# pc_healthypi_5_3.net
KiCad netlist of a schematic drawn in EAGLE
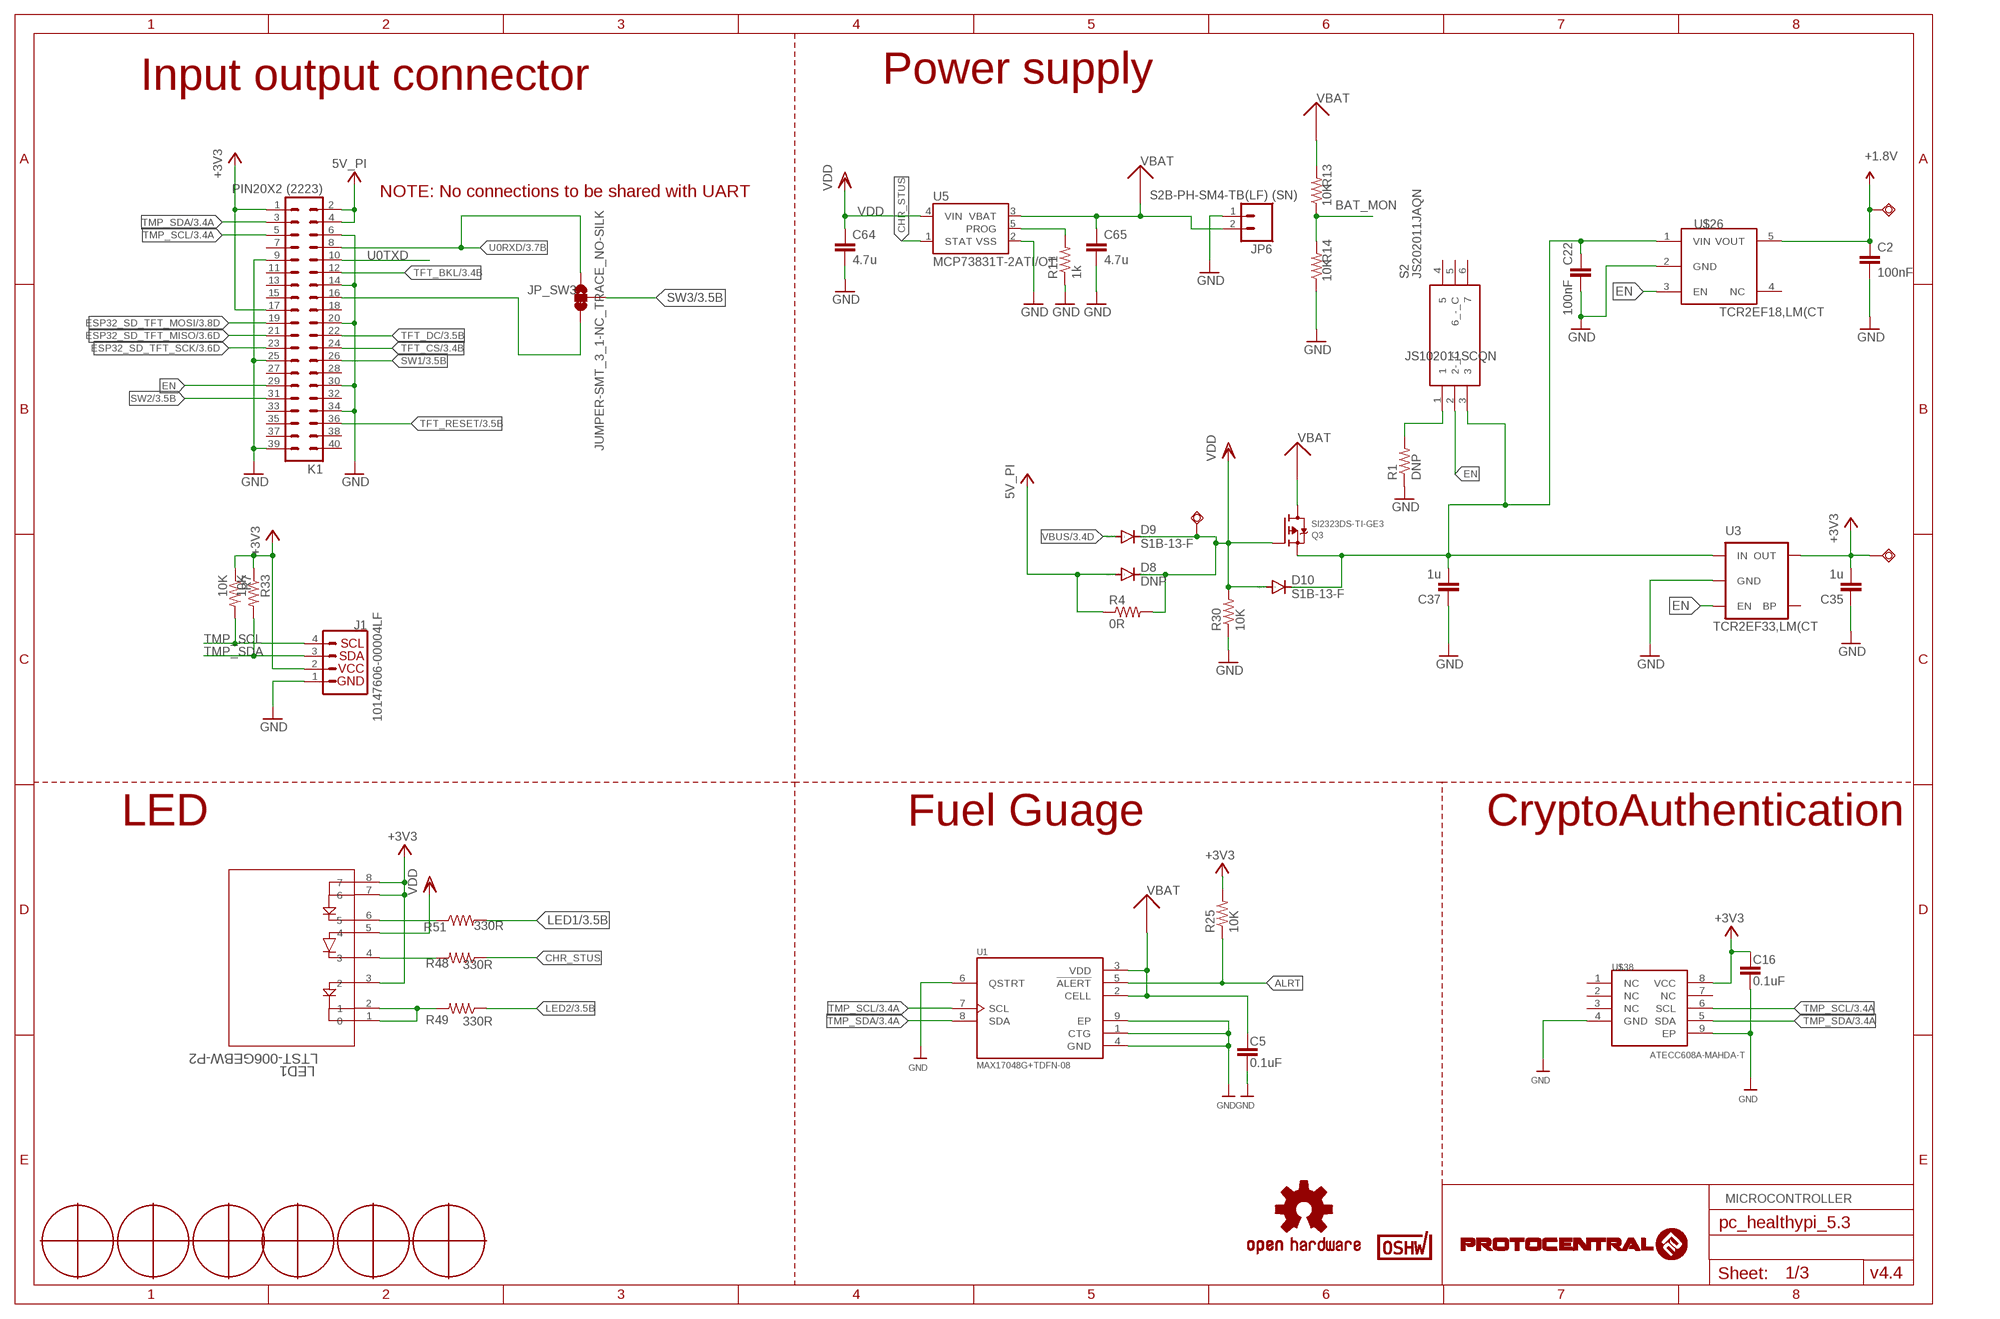
[diagram p0: schematic, sheet 1]
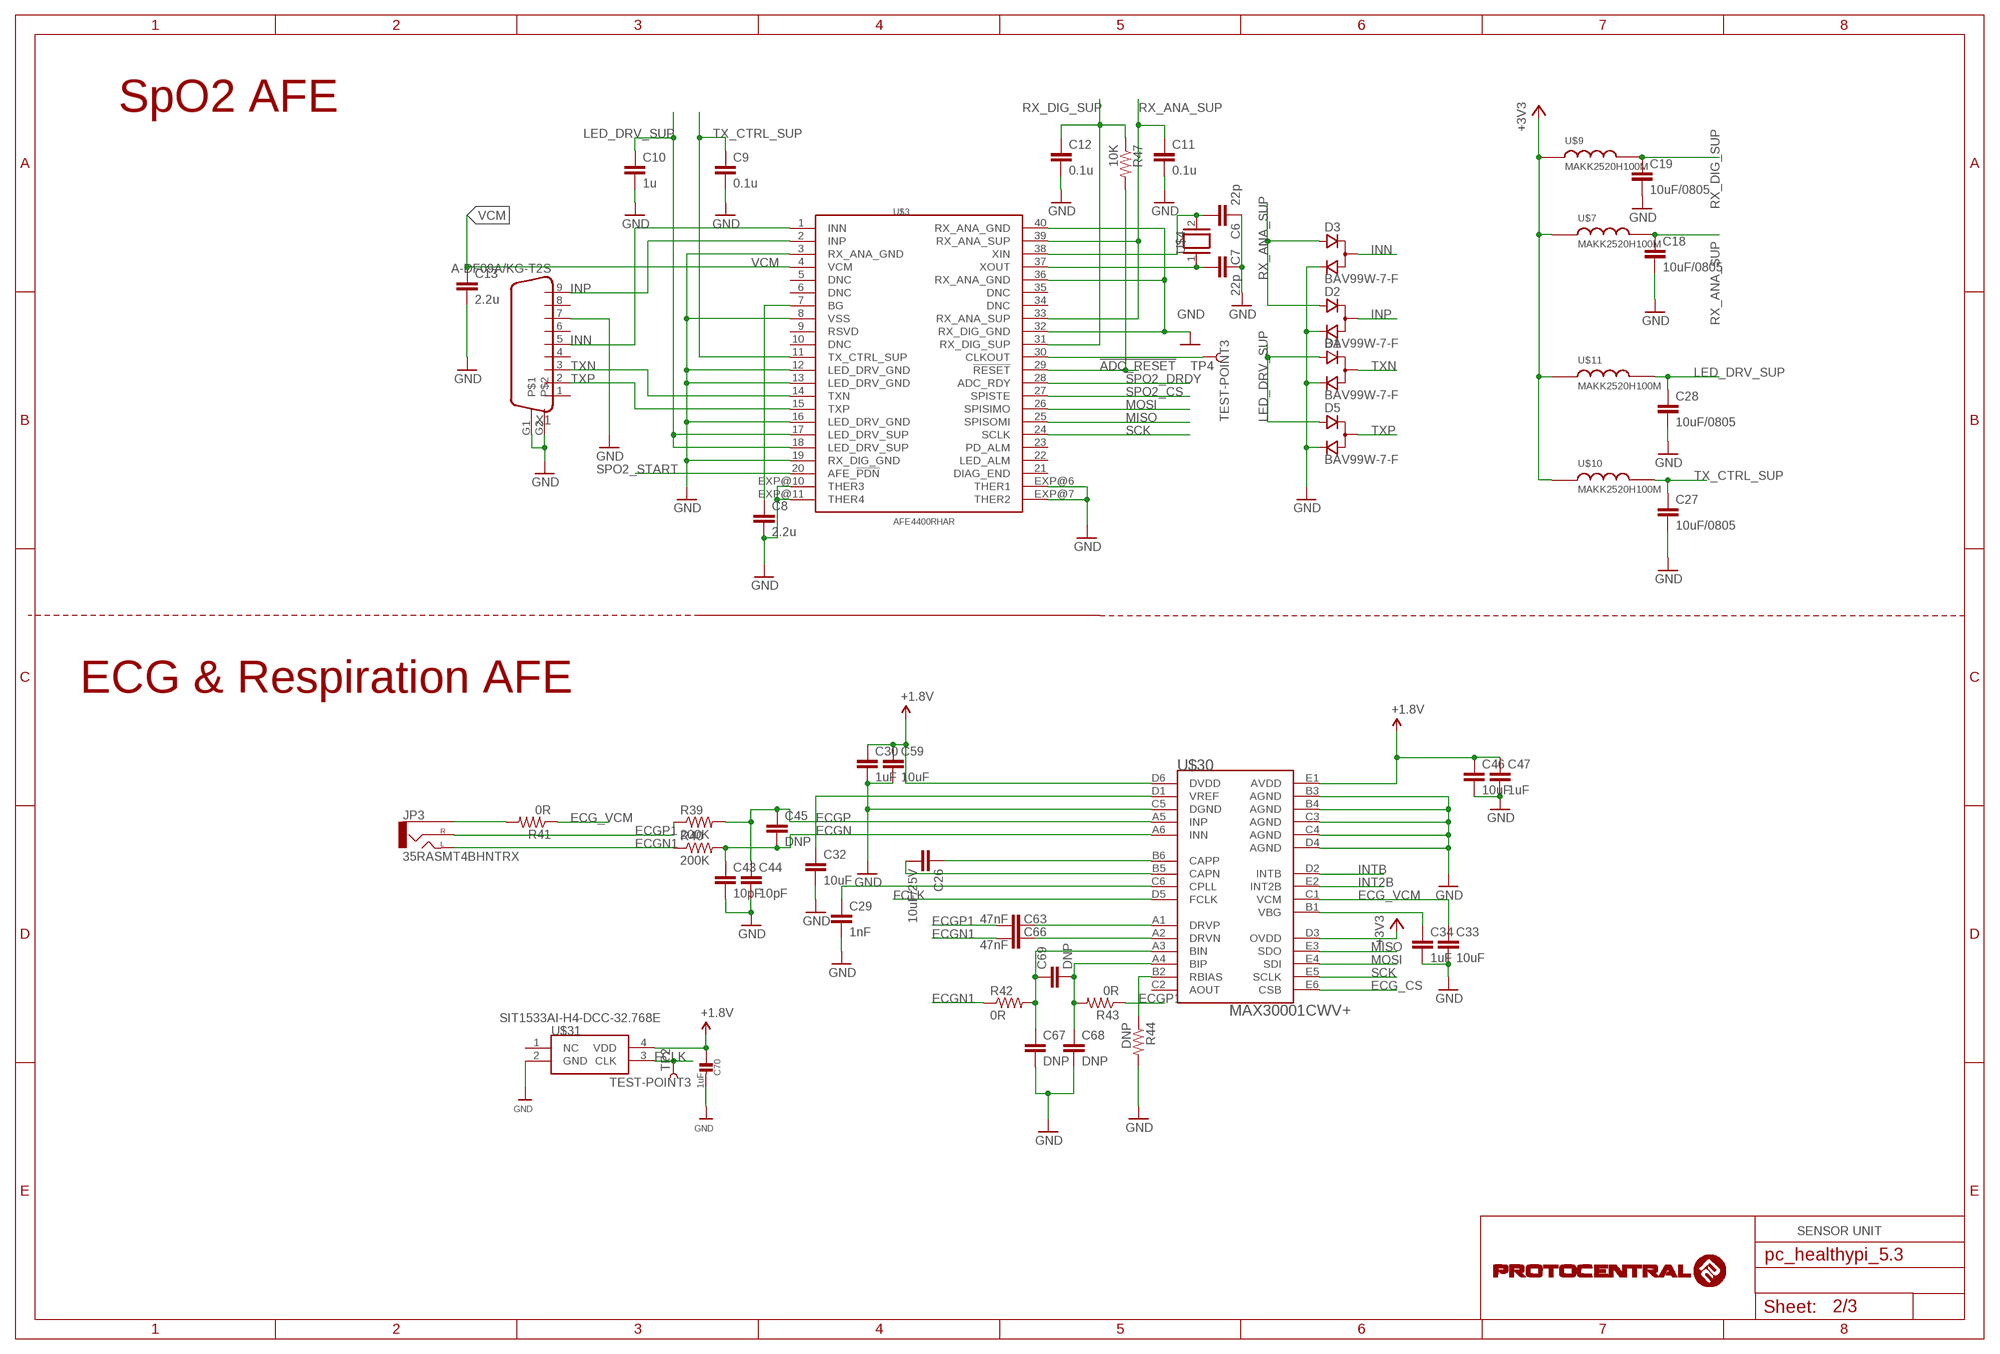
[diagram p1: schematic, sheet 2]
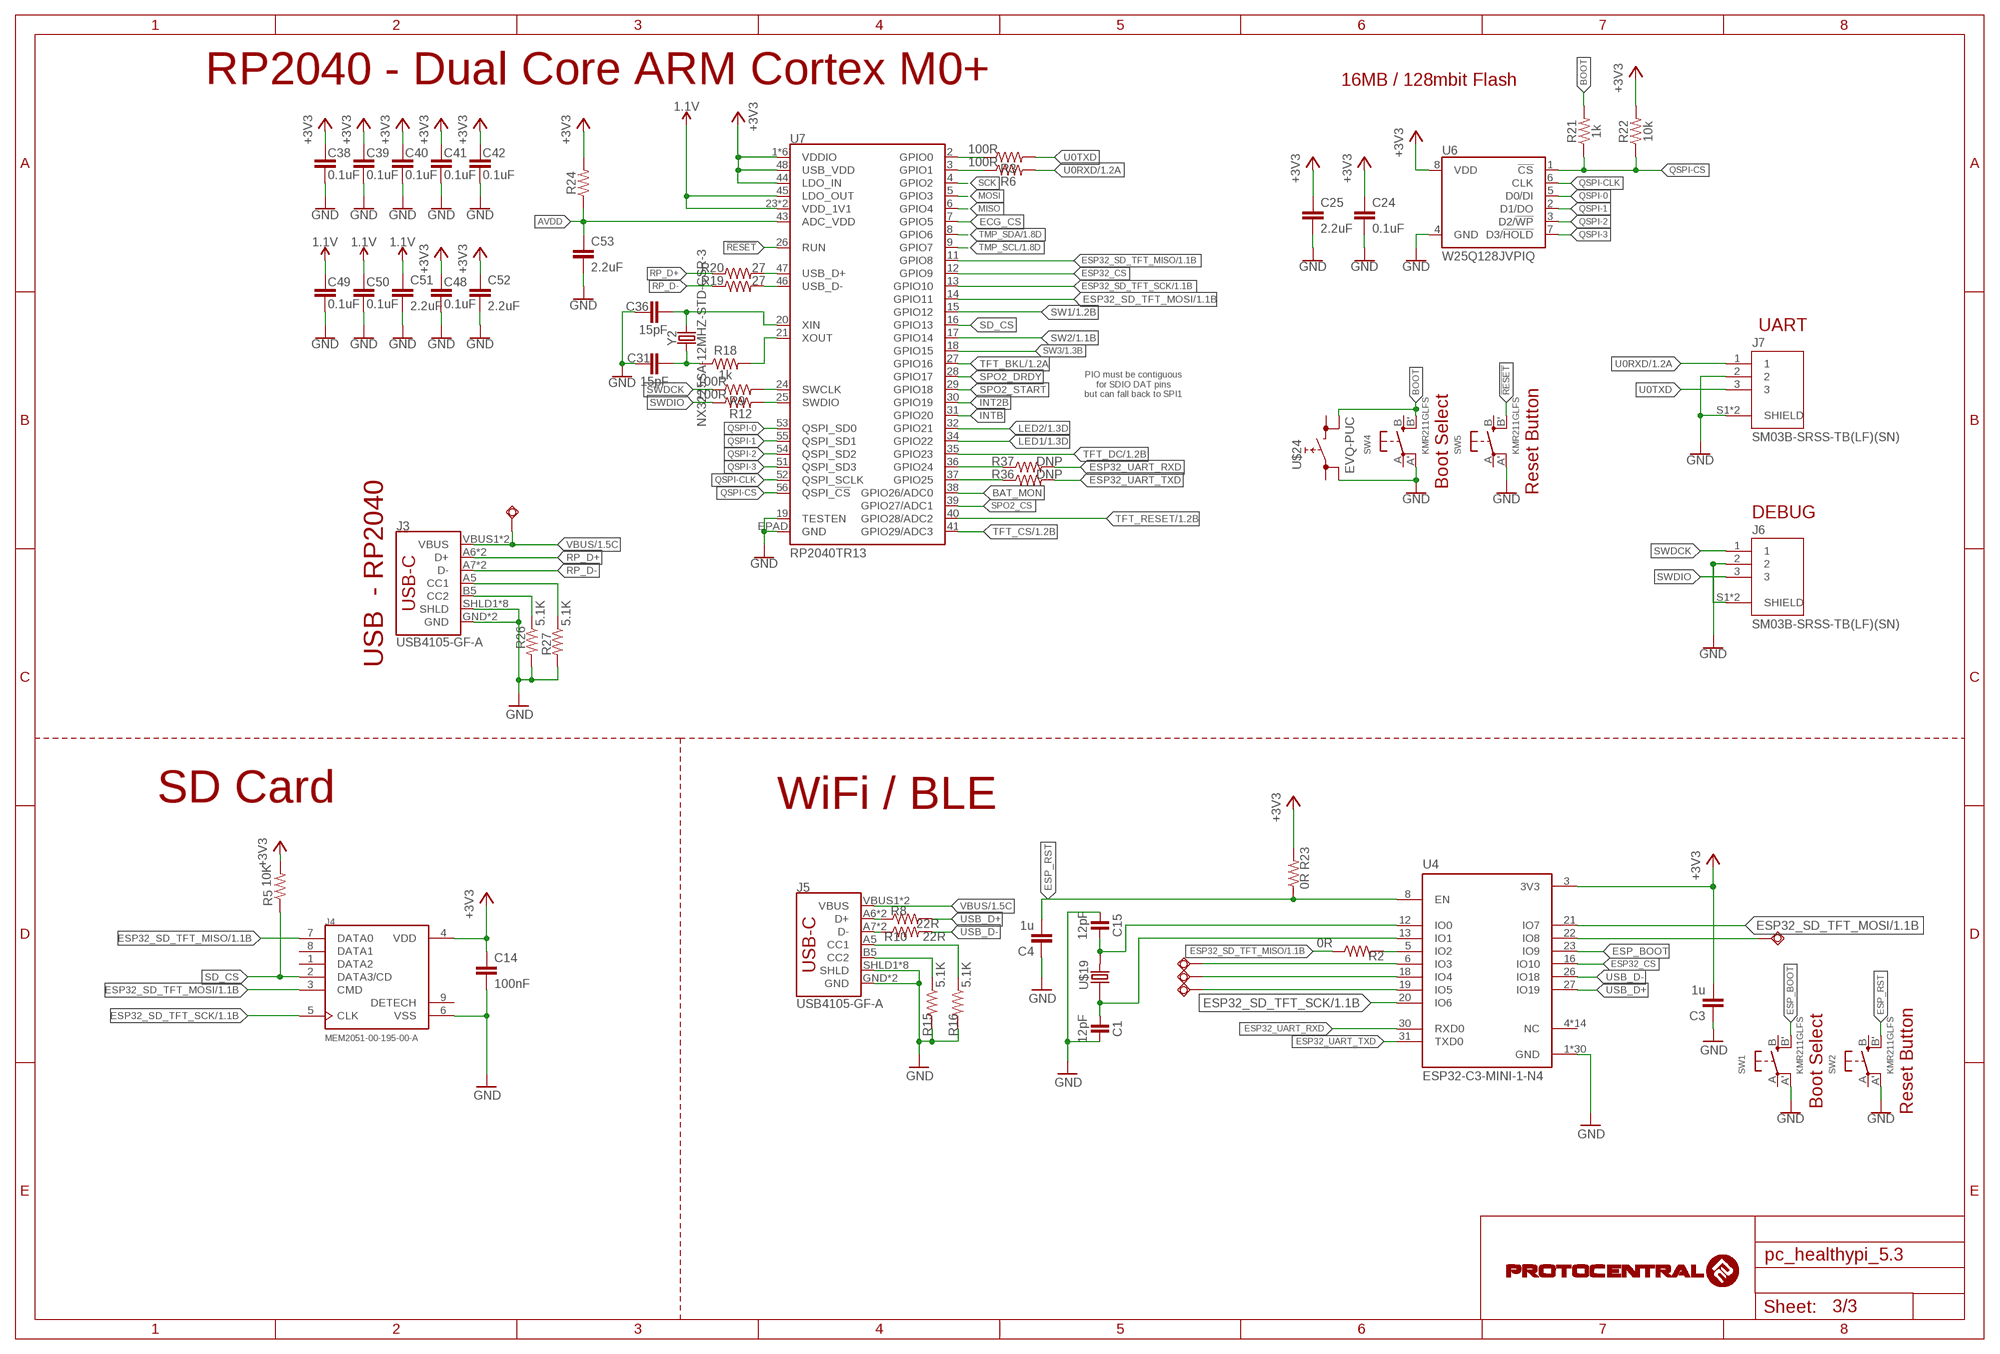
[diagram p2: schematic, sheet 3]

(export (version "E")
  (design (tool "Eeschema 10.0.6"))
  (components
    (comp (ref "C2")
      (value "100nF")
      (footprint "eagle-import:C0402")
      (libsource (lib "eagle-import") (part "rcl_334_C-EUC0402"))
    )
    (comp (ref "C5")
      (value "0.1uF")
      (footprint "eagle-import:0402-TIGHT")
      (libsource (lib "eagle-import") (part "0.1UF-0402T-6.3V-10%-X7R"))
    )
    (comp (ref "C16")
      (value "0.1uF")
      (footprint "eagle-import:0402-TIGHT")
      (libsource (lib "eagle-import") (part "0.1UF-0402T-6.3V-10%-X7R"))
    )
    (comp (ref "C22")
      (value "100nF")
      (footprint "eagle-import:C0402")
      (libsource (lib "eagle-import") (part "rcl_334_C-EUC0402"))
    )
    (comp (ref "C35")
      (value "1u")
      (footprint "eagle-import:C0402")
      (libsource (lib "eagle-import") (part "rcl_334_C-EUC0402"))
    )
    (comp (ref "C37")
      (value "1u")
      (footprint "eagle-import:C0402")
      (libsource (lib "eagle-import") (part "rcl_334_C-EUC0402"))
    )
    (comp (ref "C64")
      (value "4.7u")
      (footprint "eagle-import:C0805")
      (libsource (lib "eagle-import") (part "rcl_334_C-EUC0805"))
    )
    (comp (ref "C65")
      (value "4.7u")
      (footprint "eagle-import:C0805")
      (libsource (lib "eagle-import") (part "rcl_334_C-EUC0805"))
    )
    (comp (ref "D8")
      (value "DNP")
      (footprint "eagle-import:SOD-123_MINI-SMA")
      (libsource (lib "eagle-import") (part "CGRM400-G1"))
    )
    (comp (ref "D9")
      (value "S1B-13-F")
      (footprint "eagle-import:SOD-123_MINI-SMA")
      (libsource (lib "eagle-import") (part "CGRM400-G1"))
    )
    (comp (ref "D10")
      (value "S1B-13-F")
      (footprint "eagle-import:SOD-123_MINI-SMA")
      (libsource (lib "eagle-import") (part "CGRM400-G1"))
    )
    (comp (ref "J1")
      (value "10147606-00004LF")
      (footprint "eagle-import:JST04_1MM_RA")
      (libsource (lib "eagle-import") (part "QWIIC_CONNECTORJS-1MM"))
    )
    (comp (ref "JP6")
      (value "S2B-PH-SM4-TB(LF) (SN)")
      (footprint "eagle-import:JST-2-SMD")
      (libsource (lib "eagle-import") (part "M02-JST-2MM-SMT"))
    )
    (comp (ref "JP_SW3")
      (value "JUMPER-SMT_3_1-NC_TRACE_NO-SILK")
      (footprint "eagle-import:SMT-JUMPER_3_1-NC_TRACE_NO-SILK")
      (libsource (lib "eagle-import") (part "JUMPER-SMT_3_1-NC_TRACE_NO-SILK"))
    )
    (comp (ref "K1")
      (value "PIN20X2 (2223)")
      (footprint "eagle-import:PIN_20X2")
      (libsource (lib "eagle-import") (part "PIN20X2"))
    )
    (comp (ref "LED1")
      (value "LTST-006GEBW-P2")
      (footprint "eagle-import:LTST-008BGEW_LTO")
      (fields (field (name "COPYRIGHT") "Copyright (C) 2023 Ultra Librarian. All rights reserved."))
      (libsource (lib "eagle-import") (part "LTST-006GEBW-P2"))
    )
    (comp (ref "Q3")
      (value "SI2323DS-TI-GE3")
      (footprint "eagle-import:SOT23-R")
      (libsource (lib "eagle-import") (part "MOSFET-P"))
    )
    (comp (ref "R1")
      (value "DNP")
      (footprint "eagle-import:R0402")
      (libsource (lib "eagle-import") (part "rcl_334_R-US_R0402"))
    )
    (comp (ref "R4")
      (value "0R")
      (footprint "eagle-import:0805")
      (libsource (lib "eagle-import") (part "RESISTOR0805-RES"))
    )
    (comp (ref "R7")
      (value "10K")
      (footprint "eagle-import:R0402")
      (libsource (lib "eagle-import") (part "rcl_334_R-US_R0402"))
    )
    (comp (ref "R11")
      (value "1k")
      (footprint "eagle-import:R0402")
      (libsource (lib "eagle-import") (part "rcl_334_R-US_R0402"))
    )
    (comp (ref "R13")
      (value "10K")
      (footprint "eagle-import:R0402")
      (libsource (lib "eagle-import") (part "rcl_334_R-US_R0402"))
    )
    (comp (ref "R14")
      (value "10K")
      (footprint "eagle-import:R0402")
      (libsource (lib "eagle-import") (part "rcl_334_R-US_R0402"))
    )
    (comp (ref "R25")
      (value "10K")
      (footprint "eagle-import:0402-RES")
      (libsource (lib "eagle-import") (part "RESISTOR0402-RES"))
    )
    (comp (ref "R30")
      (value "10K")
      (footprint "eagle-import:R0402")
      (libsource (lib "eagle-import") (part "rcl_334_R-US_R0402"))
    )
    (comp (ref "R33")
      (value "10K")
      (footprint "eagle-import:R0402")
      (libsource (lib "eagle-import") (part "rcl_334_R-US_R0402"))
    )
    (comp (ref "R48")
      (value "330R")
      (footprint "eagle-import:0402-RES")
      (libsource (lib "eagle-import") (part "RESISTOR0402-RES"))
    )
    (comp (ref "R49")
      (value "330R")
      (footprint "eagle-import:0402-RES")
      (libsource (lib "eagle-import") (part "RESISTOR0402-RES"))
    )
    (comp (ref "R51")
      (value "330R")
      (footprint "eagle-import:0402-RES")
      (libsource (lib "eagle-import") (part "RESISTOR0402-RES"))
    )
    (comp (ref "S2")
      (value "JS202011JAQN")
      (footprint "eagle-import:JS202011JAQN")
      (fields (field (name "MF") "C&K"))
      (libsource (lib "eagle-import") (part "JS202011JAQN"))
    )
    (comp (ref "SWIO1")
      (value "TPSQTP11R")
      (footprint "eagle-import:TP11R")
      (libsource (lib "eagle-import") (part "TPSQTP11R"))
    )
    (comp (ref "SWIO5")
      (value "TPSQTP11R")
      (footprint "eagle-import:TP11R")
      (libsource (lib "eagle-import") (part "TPSQTP11R"))
    )
    (comp (ref "SWIO7")
      (value "TPSQTP11R")
      (footprint "eagle-import:TP11R")
      (libsource (lib "eagle-import") (part "TPSQTP11R"))
    )
    (comp (ref "U$1")
      (value "FUDCIALPOINTS")
      (footprint "eagle-import:FIDUCIALPOINTS")
      (libsource (lib "eagle-import") (part "circuitects_38825256_FUDCIALPOINTS"))
    )
    (comp (ref "U$5")
      (value "OSHW-LOGOM")
      (footprint "eagle-import:OSHW-LOGO-M")
      (libsource (lib "eagle-import") (part "OSHW-LOGOM"))
    )
    (comp (ref "U$13")
      (value "CERT-SMALL")
      (footprint "eagle-import:CERT-SMALL-SILK")
      (libsource (lib "eagle-import") (part "CERT-SMALL"))
    )
    (comp (ref "U$21")
      (value "FUDCIALPOINTS")
      (footprint "eagle-import:FIDUCIALPOINTS")
      (libsource (lib "eagle-import") (part "FUDCIALPOINTS"))
    )
    (comp (ref "U$23")
      (value "FUDCIALPOINTS")
      (footprint "eagle-import:FIDUCIALPOINTS")
      (libsource (lib "eagle-import") (part "circuitects_38825256_FUDCIALPOINTS"))
    )
    (comp (ref "U$25")
      (value "FUDCIALPOINTS")
      (footprint "eagle-import:FIDUCIALPOINTS")
      (libsource (lib "eagle-import") (part "circuitects_38825256_FUDCIALPOINTS"))
    )
    (comp (ref "U$26")
      (value "TCR2EF18,LM(CT")
      (footprint "eagle-import:SOT95P285X140-5N")
      (libsource (lib "eagle-import") (part "AP7354D-18W5-7"))
    )
    (comp (ref "U$28")
      (value "FUDCIALPOINTS")
      (footprint "eagle-import:FIDUCIALPOINTS")
      (libsource (lib "eagle-import") (part "FUDCIALPOINTS"))
    )
    (comp (ref "U$29")
      (value "FUDCIALPOINTS")
      (footprint "eagle-import:FIDUCIALPOINTS")
      (libsource (lib "eagle-import") (part "FUDCIALPOINTS"))
    )
    (comp (ref "U$38")
      (value "ATECC608A-MAHDA-T")
      (footprint "eagle-import:PSON50P200X300X60-9N")
      (libsource (lib "eagle-import") (part "ATECC608B-TFLXTLS"))
    )
    (comp (ref "U1")
      (value "MAX17048G+TDFN-08")
      (footprint "eagle-import:SON50P200X200X80-9N")
      (fields (field (name "MF") "Analog Devices") (field (name "MP") "MAX17048G+"))
      (libsource (lib "eagle-import") (part "MAX17048G+TDFN-08"))
    )
    (comp (ref "U3")
      (value "TCR2EF33,LM(CT")
      (footprint "eagle-import:SOT23-5")
      (libsource (lib "eagle-import") (part "V_REG_LDOSMD"))
    )
    (comp (ref "U5")
      (value "MCP73831T-2ATI/OT")
      (footprint "eagle-import:SOT23-5")
      (libsource (lib "eagle-import") (part "MCP73831"))
    )
    (comp (ref "C6")
      (value "22p")
      (footprint "eagle-import:C0402")
      (libsource (lib "eagle-import") (part "rcl_334_C-EUC0402"))
    )
    (comp (ref "C7")
      (value "22p")
      (footprint "eagle-import:C0402")
      (libsource (lib "eagle-import") (part "rcl_334_C-EUC0402"))
    )
    (comp (ref "C8")
      (value "2.2u")
      (footprint "eagle-import:C0402")
      (libsource (lib "eagle-import") (part "rcl_334_C-EUC0402"))
    )
    (comp (ref "C9")
      (value "0.1u")
      (footprint "eagle-import:C0402")
      (libsource (lib "eagle-import") (part "rcl_334_C-EUC0402"))
    )
    (comp (ref "C10")
      (value "1u")
      (footprint "eagle-import:C0805")
      (libsource (lib "eagle-import") (part "rcl_334_C-EUC0805"))
    )
    (comp (ref "C11")
      (value "0.1u")
      (footprint "eagle-import:C0402")
      (libsource (lib "eagle-import") (part "rcl_334_C-EUC0402"))
    )
    (comp (ref "C12")
      (value "0.1u")
      (footprint "eagle-import:C0402")
      (libsource (lib "eagle-import") (part "rcl_334_C-EUC0402"))
    )
    (comp (ref "C13")
      (value "2.2u")
      (footprint "eagle-import:C0402")
      (libsource (lib "eagle-import") (part "rcl_334_C-EUC0402"))
    )
    (comp (ref "C18")
      (value "10uF/0805")
      (footprint "eagle-import:C0805")
      (libsource (lib "eagle-import") (part "rcl_334_C-EUC0805"))
    )
    (comp (ref "C19")
      (value "10uF/0805")
      (footprint "eagle-import:C0805")
      (libsource (lib "eagle-import") (part "rcl_334_C-EUC0805"))
    )
    (comp (ref "C26")
      (value "10uF/25V")
      (footprint "eagle-import:C0805")
      (libsource (lib "eagle-import") (part "rcl_334_C-EUC0805"))
    )
    (comp (ref "C27")
      (value "10uF/0805")
      (footprint "eagle-import:C0805")
      (libsource (lib "eagle-import") (part "rcl_334_C-EUC0805"))
    )
    (comp (ref "C28")
      (value "10uF/0805")
      (footprint "eagle-import:C0805")
      (libsource (lib "eagle-import") (part "rcl_334_C-EUC0805"))
    )
    (comp (ref "C29")
      (value "1nF")
      (footprint "eagle-import:C0402")
      (libsource (lib "eagle-import") (part "rcl_334_C-EUC0402"))
    )
    (comp (ref "C30")
      (value "1uF")
      (footprint "eagle-import:C0402")
      (libsource (lib "eagle-import") (part "rcl_334_C-EUC0402"))
    )
    (comp (ref "C32")
      (value "10uF")
      (footprint "eagle-import:C0805")
      (libsource (lib "eagle-import") (part "rcl_334_C-EUC0805"))
    )
    (comp (ref "C33")
      (value "10uF")
      (footprint "eagle-import:C0805")
      (libsource (lib "eagle-import") (part "rcl_334_C-EUC0805"))
    )
    (comp (ref "C34")
      (value "1uF")
      (footprint "eagle-import:C0402")
      (libsource (lib "eagle-import") (part "rcl_334_C-EUC0402"))
    )
    (comp (ref "C43")
      (value "10pF")
      (footprint "eagle-import:C0402")
      (libsource (lib "eagle-import") (part "rcl_334_C-EUC0402"))
    )
    (comp (ref "C44")
      (value "10pF")
      (footprint "eagle-import:C0402")
      (libsource (lib "eagle-import") (part "rcl_334_C-EUC0402"))
    )
    (comp (ref "C45")
      (value "DNP")
      (footprint "eagle-import:C0402")
      (libsource (lib "eagle-import") (part "rcl_334_C-EUC0402"))
    )
    (comp (ref "C46")
      (value "10uF")
      (footprint "eagle-import:C0805")
      (libsource (lib "eagle-import") (part "rcl_334_C-EUC0805"))
    )
    (comp (ref "C47")
      (value "1uF")
      (footprint "eagle-import:C0402")
      (libsource (lib "eagle-import") (part "rcl_334_C-EUC0402"))
    )
    (comp (ref "C59")
      (value "10uF")
      (footprint "eagle-import:C0805")
      (libsource (lib "eagle-import") (part "rcl_334_C-EUC0805"))
    )
    (comp (ref "C63")
      (value "47nF")
      (footprint "eagle-import:C0402")
      (libsource (lib "eagle-import") (part "rcl_334_C-EUC0402"))
    )
    (comp (ref "C66")
      (value "47nF")
      (footprint "eagle-import:C0402")
      (libsource (lib "eagle-import") (part "rcl_334_C-EUC0402"))
    )
    (comp (ref "C67")
      (value "DNP")
      (footprint "eagle-import:C0402")
      (libsource (lib "eagle-import") (part "rcl_334_C-EUC0402"))
    )
    (comp (ref "C68")
      (value "DNP")
      (footprint "eagle-import:C0402")
      (libsource (lib "eagle-import") (part "rcl_334_C-EUC0402"))
    )
    (comp (ref "C69")
      (value "DNP")
      (footprint "eagle-import:C0402")
      (libsource (lib "eagle-import") (part "rcl_334_C-EUC0402"))
    )
    (comp (ref "C70")
      (value "1uF")
      (footprint "eagle-import:0402")
      (libsource (lib "eagle-import") (part "CAP_CERAMIC0402"))
    )
    (comp (ref "D1")
      (value "BAV99W-7-F")
      (footprint "eagle-import:SOT323")
      (libsource (lib "eagle-import") (part "D_ACACSOT323"))
    )
    (comp (ref "D2")
      (value "BAV99W-7-F")
      (footprint "eagle-import:SOT323")
      (libsource (lib "eagle-import") (part "D_ACACSOT323"))
    )
    (comp (ref "D3")
      (value "BAV99W-7-F")
      (footprint "eagle-import:SOT323")
      (libsource (lib "eagle-import") (part "D_ACACSOT323"))
    )
    (comp (ref "D5")
      (value "BAV99W-7-F")
      (footprint "eagle-import:SOT323")
      (libsource (lib "eagle-import") (part "D_ACACSOT323"))
    )
    (comp (ref "JP3")
      (value "35RASMT4BHNTRX")
      (footprint "eagle-import:AUDIO-JACK-3.5MM-SMD")
      (libsource (lib "eagle-import") (part "AUDIO-JACKSMD2"))
    )
    (comp (ref "R39")
      (value "200K")
      (footprint "eagle-import:0805")
      (libsource (lib "eagle-import") (part "RESISTOR0805-RES"))
    )
    (comp (ref "R40")
      (value "200K")
      (footprint "eagle-import:0805")
      (libsource (lib "eagle-import") (part "RESISTOR0805-RES"))
    )
    (comp (ref "R41")
      (value "0R")
      (footprint "eagle-import:0805")
      (libsource (lib "eagle-import") (part "RESISTOR0805-RES"))
    )
    (comp (ref "R42")
      (value "0R")
      (footprint "eagle-import:0402-RES")
      (libsource (lib "eagle-import") (part "RESISTOR0402-RES"))
    )
    (comp (ref "R43")
      (value "0R")
      (footprint "eagle-import:0402-RES")
      (libsource (lib "eagle-import") (part "RESISTOR0402-RES"))
    )
    (comp (ref "R44")
      (value "DNP")
      (footprint "eagle-import:0402-RES")
      (libsource (lib "eagle-import") (part "RESISTOR0402-RES"))
    )
    (comp (ref "R47")
      (value "10K")
      (footprint "eagle-import:R0402")
      (libsource (lib "eagle-import") (part "rcl_334_R-US_R0402"))
    )
    (comp (ref "TP2")
      (value "TEST-POINT3")
      (footprint "eagle-import:PAD.03X.03")
      (libsource (lib "eagle-import") (part "TEST-POINT3"))
    )
    (comp (ref "TP4")
      (value "TEST-POINT3")
      (footprint "eagle-import:PAD.03X.03")
      (libsource (lib "eagle-import") (part "TEST-POINT3"))
    )
    (comp (ref "U$3")
      (value "AFE4400RHAR")
      (footprint "eagle-import:QFN-40")
      (libsource (lib "eagle-import") (part "AFE4400"))
    )
    (comp (ref "U$4")
      (value "HC-49/U-S16000000ABJB")
      (footprint "eagle-import:XTAL_HC49P488W43L1150T466H350")
      (fields (field (name "MF") "Citizen Finedevice Co Ltd"))
      (libsource (lib "eagle-import") (part "HC-49/U-S16000000ABJB"))
    )
    (comp (ref "U$7")
      (value "MAKK2520H100M")
      (footprint "eagle-import:LPS")
      (libsource (lib "eagle-import") (part "LPS"))
    )
    (comp (ref "U$9")
      (value "MAKK2520H100M")
      (footprint "eagle-import:LPS")
      (libsource (lib "eagle-import") (part "LPS"))
    )
    (comp (ref "U$10")
      (value "MAKK2520H100M")
      (footprint "eagle-import:LPS")
      (libsource (lib "eagle-import") (part "LPS"))
    )
    (comp (ref "U$11")
      (value "MAKK2520H100M")
      (footprint "eagle-import:LPS")
      (libsource (lib "eagle-import") (part "LPS"))
    )
    (comp (ref "U$30")
      (value "MAX30001CWV+")
      (footprint "eagle-import:30WLP")
      (libsource (lib "eagle-import") (part "MAX30001CWV+"))
    )
    (comp (ref "U$31")
      (value "SIT1533AI-H4-DCC-32.768E")
      (footprint "eagle-import:SIT1533")
      (libsource (lib "eagle-import") (part "SIT1533"))
    )
    (comp (ref "X1")
      (value "A-DF09A/KG-T2S")
      (footprint "eagle-import:DB9")
      (libsource (lib "eagle-import") (part "DB9"))
    )
    (comp (ref "C1")
      (value "12pF")
      (footprint "eagle-import:C0402")
      (libsource (lib "eagle-import") (part "CAPACITORS-0402"))
    )
    (comp (ref "C3")
      (value "1u")
      (footprint "eagle-import:C0402")
      (libsource (lib "eagle-import") (part "rcl_334_C-EUC0402"))
    )
    (comp (ref "C4")
      (value "1u")
      (footprint "eagle-import:C0402")
      (libsource (lib "eagle-import") (part "rcl_334_C-EUC0402"))
    )
    (comp (ref "C14")
      (value "100nF")
      (footprint "eagle-import:C0402")
      (libsource (lib "eagle-import") (part "C-EUC0402"))
    )
    (comp (ref "C15")
      (value "12pF")
      (footprint "eagle-import:C0402")
      (libsource (lib "eagle-import") (part "CAPACITORS-0402"))
    )
    (comp (ref "C24")
      (value "0.1uF")
      (footprint "eagle-import:0402-TIGHT")
      (libsource (lib "eagle-import") (part "0.1UF-0402T-6.3V-10%-X7R"))
    )
    (comp (ref "C25")
      (value "2.2uF")
      (footprint "eagle-import:0402-TIGHT")
      (libsource (lib "eagle-import") (part "2.2UF-0402_TIGHT-10V-10%-X5R"))
    )
    (comp (ref "C31")
      (value "15pF")
      (footprint "eagle-import:0402-TIGHT")
      (libsource (lib "eagle-import") (part "15PF-0402T-50V-5%"))
    )
    (comp (ref "C36")
      (value "15pF")
      (footprint "eagle-import:0402-TIGHT")
      (libsource (lib "eagle-import") (part "15PF-0402T-50V-5%"))
    )
    (comp (ref "C38")
      (value "0.1uF")
      (footprint "eagle-import:0402-TIGHT")
      (libsource (lib "eagle-import") (part "0.1UF-0402T-6.3V-10%-X7R"))
    )
    (comp (ref "C39")
      (value "0.1uF")
      (footprint "eagle-import:0402-TIGHT")
      (libsource (lib "eagle-import") (part "0.1UF-0402T-6.3V-10%-X7R"))
    )
    (comp (ref "C40")
      (value "0.1uF")
      (footprint "eagle-import:0402-TIGHT")
      (libsource (lib "eagle-import") (part "0.1UF-0402T-6.3V-10%-X7R"))
    )
    (comp (ref "C41")
      (value "0.1uF")
      (footprint "eagle-import:0402-TIGHT")
      (libsource (lib "eagle-import") (part "0.1UF-0402T-6.3V-10%-X7R"))
    )
    (comp (ref "C42")
      (value "0.1uF")
      (footprint "eagle-import:0402-TIGHT")
      (libsource (lib "eagle-import") (part "0.1UF-0402T-6.3V-10%-X7R"))
    )
    (comp (ref "C48")
      (value "0.1uF")
      (footprint "eagle-import:0402-TIGHT")
      (libsource (lib "eagle-import") (part "0.1UF-0402T-6.3V-10%-X7R"))
    )
    (comp (ref "C49")
      (value "0.1uF")
      (footprint "eagle-import:0402-TIGHT")
      (libsource (lib "eagle-import") (part "0.1UF-0402T-6.3V-10%-X7R"))
    )
    (comp (ref "C50")
      (value "0.1uF")
      (footprint "eagle-import:0402-TIGHT")
      (libsource (lib "eagle-import") (part "0.1UF-0402T-6.3V-10%-X7R"))
    )
    (comp (ref "C51")
      (value "2.2uF")
      (footprint "eagle-import:0402-TIGHT")
      (libsource (lib "eagle-import") (part "2.2UF-0402_TIGHT-10V-10%-X5R"))
    )
    (comp (ref "C52")
      (value "2.2uF")
      (footprint "eagle-import:0402-TIGHT")
      (libsource (lib "eagle-import") (part "2.2UF-0402_TIGHT-10V-10%-X5R"))
    )
    (comp (ref "C53")
      (value "2.2uF")
      (footprint "eagle-import:0402-TIGHT")
      (libsource (lib "eagle-import") (part "2.2UF-0402_TIGHT-10V-10%-X5R"))
    )
    (comp (ref "J3")
      (value "USB4105-GF-A")
      (footprint "eagle-import:USB-C-16P")
      (libsource (lib "eagle-import") (part "USB_C16PIN"))
    )
    (comp (ref "J4")
      (value "MEM2051-00-195-00-A")
      (footprint "eagle-import:GCT_MEM2051-00-195-00-A")
      (fields (field (name "MF") "Global Connector Technology"))
      (libsource (lib "eagle-import") (part "MEM2051-00-195-00-A"))
    )
    (comp (ref "J5")
      (value "USB4105-GF-A")
      (footprint "eagle-import:USB-C-16P")
      (libsource (lib "eagle-import") (part "circuitects_38825256_USB_C16PIN"))
    )
    (comp (ref "J6")
      (value "SM03B-SRSS-TB(LF)(SN)")
      (footprint "eagle-import:JST_SM03B-SRSS-TB(LF)(SN)")
      (fields (field (name "MF") "JST Sales America Inc."))
      (libsource (lib "eagle-import") (part "SM03B-SRSS-TB(LF)(SN)"))
    )
    (comp (ref "J7")
      (value "SM03B-SRSS-TB(LF)(SN)")
      (footprint "eagle-import:JST_SM03B-SRSS-TB(LF)(SN)")
      (fields (field (name "MF") "JST Sales America Inc."))
      (libsource (lib "eagle-import") (part "SM03B-SRSS-TB(LF)(SN)"))
    )
    (comp (ref "R2")
      (value "0R")
      (footprint "eagle-import:R0402")
      (libsource (lib "eagle-import") (part "rcl_334_R-US_R0402"))
    )
    (comp (ref "R3")
      (value "100R")
      (footprint "eagle-import:R0402")
      (libsource (lib "eagle-import") (part "rcl_334_R-US_R0402"))
    )
    (comp (ref "R5")
      (value "10K")
      (footprint "eagle-import:R0402")
      (libsource (lib "eagle-import") (part "R-US_R0402"))
    )
    (comp (ref "R6")
      (value "100R")
      (footprint "eagle-import:R0402")
      (libsource (lib "eagle-import") (part "rcl_334_R-US_R0402"))
    )
    (comp (ref "R8")
      (value "22R")
      (footprint "eagle-import:R0402")
      (libsource (lib "eagle-import") (part "rcl_334_R-US_R0402"))
    )
    (comp (ref "R9")
      (value "100R")
      (footprint "eagle-import:R0402")
      (libsource (lib "eagle-import") (part "rcl_334_R-US_R0402"))
    )
    (comp (ref "R10")
      (value "22R")
      (footprint "eagle-import:R0402")
      (libsource (lib "eagle-import") (part "rcl_334_R-US_R0402"))
    )
    (comp (ref "R12")
      (value "100R")
      (footprint "eagle-import:R0402")
      (libsource (lib "eagle-import") (part "rcl_334_R-US_R0402"))
    )
    (comp (ref "R15")
      (value "5.1K")
      (footprint "eagle-import:R0402")
      (libsource (lib "eagle-import") (part "rcl_334_R-US_R0402"))
    )
    (comp (ref "R16")
      (value "5.1K")
      (footprint "eagle-import:R0402")
      (libsource (lib "eagle-import") (part "rcl_334_R-US_R0402"))
    )
    (comp (ref "R18")
      (value "1k")
      (footprint "eagle-import:0402-TIGHT")
      (libsource (lib "eagle-import") (part "1KOHM-0402T-1/16W-1%"))
    )
    (comp (ref "R19")
      (value "27")
      (footprint "eagle-import:0402-TIGHT")
      (libsource (lib "eagle-import") (part "27OHM"))
    )
    (comp (ref "R20")
      (value "27")
      (footprint "eagle-import:0402-TIGHT")
      (libsource (lib "eagle-import") (part "27OHM"))
    )
    (comp (ref "R21")
      (value "1k")
      (footprint "eagle-import:0402-TIGHT")
      (libsource (lib "eagle-import") (part "1KOHM-0402T-1/16W-1%"))
    )
    (comp (ref "R22")
      (value "10k")
      (footprint "eagle-import:0402-TIGHT")
      (libsource (lib "eagle-import") (part "10KOHM-0402T-1/16W-1%"))
    )
    (comp (ref "R23")
      (value "0R")
      (footprint "eagle-import:R0402")
      (libsource (lib "eagle-import") (part "rcl_334_R-US_R0402"))
    )
    (comp (ref "R24")
      (value "200OHM-0402T-1/16W-1%")
      (footprint "eagle-import:0402-TIGHT")
      (libsource (lib "eagle-import") (part "200OHM-0402T-1/16W-1%"))
    )
    (comp (ref "R26")
      (value "5.1K")
      (footprint "eagle-import:R0402")
      (libsource (lib "eagle-import") (part "rcl_334_R-US_R0402"))
    )
    (comp (ref "R27")
      (value "5.1K")
      (footprint "eagle-import:R0402")
      (libsource (lib "eagle-import") (part "rcl_334_R-US_R0402"))
    )
    (comp (ref "R36")
      (value "DNP")
      (footprint "eagle-import:0402-TIGHT")
      (libsource (lib "eagle-import") (part "27OHM"))
    )
    (comp (ref "R37")
      (value "DNP")
      (footprint "eagle-import:0402-TIGHT")
      (libsource (lib "eagle-import") (part "27OHM"))
    )
    (comp (ref "SW1")
      (value "KMR211GLFS")
      (footprint "eagle-import:BTN_KMR2_4.6X2.8")
      (libsource (lib "eagle-import") (part "SWITCH_TACT_SMT4.6X2.8"))
    )
    (comp (ref "SW2")
      (value "KMR211GLFS")
      (footprint "eagle-import:BTN_KMR2_4.6X2.8")
      (libsource (lib "eagle-import") (part "SWITCH_TACT_SMT4.6X2.8"))
    )
    (comp (ref "SW4")
      (value "KMR211GLFS")
      (footprint "eagle-import:BTN_KMR2_4.6X2.8")
      (libsource (lib "eagle-import") (part "SWITCH_TACT_SMT4.6X2.8"))
    )
    (comp (ref "SW5")
      (value "KMR211GLFS")
      (footprint "eagle-import:BTN_KMR2_4.6X2.8")
      (libsource (lib "eagle-import") (part "SWITCH_TACT_SMT4.6X2.8"))
    )
    (comp (ref "SWIO2")
      (value "TPSQTP11R")
      (footprint "eagle-import:TP11R")
      (libsource (lib "eagle-import") (part "TPSQTP11R"))
    )
    (comp (ref "SWIO3")
      (value "TPSQTP11R")
      (footprint "eagle-import:TP11R")
      (libsource (lib "eagle-import") (part "TPSQTP11R"))
    )
    (comp (ref "SWIO4")
      (value "TPSQTP11R")
      (footprint "eagle-import:TP11R")
      (libsource (lib "eagle-import") (part "TPSQTP11R"))
    )
    (comp (ref "SWIO6")
      (value "TPSQTP11R")
      (footprint "eagle-import:TP11R")
      (libsource (lib "eagle-import") (part "TPSQTP11R"))
    )
    (comp (ref "TP5")
      (value "TPSQTP11R")
      (footprint "eagle-import:TP11R")
      (libsource (lib "eagle-import") (part "TPSQTP11R"))
    )
    (comp (ref "U$19")
      (value "520-327-12.5-34B(32.768KHZ)")
      (footprint "eagle-import:ECX-31B")
      (libsource (lib "eagle-import") (part "ECS-X-34B"))
    )
    (comp (ref "U$24")
      (value "EVQ-PUC")
      (footprint "eagle-import:EVQ-PUC")
      (libsource (lib "eagle-import") (part "EVQ-PUC"))
    )
    (comp (ref "U4")
      (value "ESP32-C3-MINI-1-N4")
      (footprint "eagle-import:XCVR_ESP32-C3-MINI-1-N4")
      (fields (field (name "MF") "Espressif Systems"))
      (libsource (lib "eagle-import") (part "ESP32-C3-MINI-1-N4"))
    )
    (comp (ref "U6")
      (value "W25Q128JVPIQ")
      (footprint "eagle-import:WSON-8-6X5-SKINNY_CENTERPAD")
      (libsource (lib "eagle-import") (part "W25QXX128MBIT-6X5-SKINNY_CENTER"))
    )
    (comp (ref "U7")
      (value "RP2040TR13")
      (footprint "eagle-import:QFN-56")
      (libsource (lib "eagle-import") (part "RP2040"))
    )
    (comp (ref "Y2")
      (value "NX3225SA-12MHZ-STD-CSR-3")
      (footprint "eagle-import:CRYSTAL-SMD-2X2.5MM")
      (libsource (lib "eagle-import") (part "CRYSTAL-12MHZ"))
    )
  )
  (nets
    (net (code "1") (name "+1.8V") (class "Default")
      (node (ref "C2") (pin "1") (pinfunction "1_1") (pintype "passive"))
      (node (ref "C30") (pin "1") (pinfunction "1_1") (pintype "passive"))
      (node (ref "C46") (pin "1") (pinfunction "1_1") (pintype "passive"))
      (node (ref "C47") (pin "1") (pinfunction "1_1") (pintype "passive"))
      (node (ref "C59") (pin "1") (pinfunction "1_1") (pintype "passive"))
      (node (ref "C70") (pin "1") (pinfunction "P$1_1") (pintype "passive"))
      (node (ref "SWIO5") (pin "TP") (pinfunction "TP_TP") (pintype "input"))
      (node (ref "U$26") (pin "5") (pinfunction "VOUT_5") (pintype "bidirectional"))
      (node (ref "U$30") (pin "D6") (pinfunction "DVDD_D6") (pintype "bidirectional"))
      (node (ref "U$30") (pin "E1") (pinfunction "AVDD_E1") (pintype "bidirectional"))
      (node (ref "U$31") (pin "4") (pinfunction "VDD_4") (pintype "bidirectional"))
    )
    (net (code "2") (name "+3V3") (class "Default")
      (node (ref "C14") (pin "1") (pinfunction "1_1") (pintype "passive"))
      (node (ref "C16") (pin "1") (pinfunction "1_1") (pintype "passive"))
      (node (ref "C24") (pin "1") (pinfunction "1_1") (pintype "passive"))
      (node (ref "C25") (pin "1") (pinfunction "1_1") (pintype "passive"))
      (node (ref "C3") (pin "2") (pinfunction "2_2") (pintype "passive"))
      (node (ref "C35") (pin "2") (pinfunction "2_2") (pintype "passive"))
      (node (ref "C38") (pin "1") (pinfunction "1_1") (pintype "passive"))
      (node (ref "C39") (pin "1") (pinfunction "1_1") (pintype "passive"))
      (node (ref "C40") (pin "1") (pinfunction "1_1") (pintype "passive"))
      (node (ref "C41") (pin "1") (pinfunction "1_1") (pintype "passive"))
      (node (ref "C42") (pin "1") (pinfunction "1_1") (pintype "passive"))
      (node (ref "C48") (pin "1") (pinfunction "1_1") (pintype "passive"))
      (node (ref "C52") (pin "1") (pinfunction "1_1") (pintype "passive"))
      (node (ref "J1") (pin "2") (pinfunction "2_2") (pintype "power_in"))
      (node (ref "J4") (pin "4") (pinfunction "VDD_4") (pintype "power_in"))
      (node (ref "K1") (pin "1") (pinfunction "1_1") (pintype "passive"))
      (node (ref "K1") (pin "17") (pinfunction "17_17") (pintype "passive"))
      (node (ref "LED1") (pin "3") (pinfunction "2_3") (pintype "passive"))
      (node (ref "LED1") (pin "7") (pinfunction "6_7") (pintype "passive"))
      (node (ref "LED1") (pin "8") (pinfunction "7_8") (pintype "passive"))
      (node (ref "R22") (pin "2") (pinfunction "2_2") (pintype "passive"))
      (node (ref "R23") (pin "2") (pinfunction "2_2") (pintype "passive"))
      (node (ref "R24") (pin "2") (pinfunction "2_2") (pintype "passive"))
      (node (ref "R25") (pin "2") (pinfunction "2_2") (pintype "passive"))
      (node (ref "R33") (pin "1") (pinfunction "1_1") (pintype "passive"))
      (node (ref "R5") (pin "2") (pinfunction "2_2") (pintype "passive"))
      (node (ref "R7") (pin "1") (pinfunction "1_1") (pintype "passive"))
      (node (ref "SWIO1") (pin "TP") (pinfunction "TP_TP") (pintype "input"))
      (node (ref "U$10") (pin "1") (pinfunction "P$1_1") (pintype "bidirectional"))
      (node (ref "U$11") (pin "1") (pinfunction "P$1_1") (pintype "bidirectional"))
      (node (ref "U$30") (pin "D3") (pinfunction "OVDD_D3") (pintype "bidirectional"))
      (node (ref "U$38") (pin "8") (pinfunction "VCC_8") (pintype "bidirectional"))
      (node (ref "U$7") (pin "1") (pinfunction "P$1_1") (pintype "bidirectional"))
      (node (ref "U$9") (pin "1") (pinfunction "P$1_1") (pintype "bidirectional"))
      (node (ref "U3") (pin "5") (pinfunction "OUT_5") (pintype "passive"))
      (node (ref "U4") (pin "3") (pinfunction "3V3_3") (pintype "power_in"))
      (node (ref "U6") (pin "8") (pinfunction "VDD_8") (pintype "bidirectional"))
      (node (ref "U7") (pin "1") (pinfunction "VDDIO_1") (pintype "bidirectional"))
      (node (ref "U7") (pin "10") (pinfunction "VDDIO_10") (pintype "bidirectional"))
      (node (ref "U7") (pin "22") (pinfunction "VDDIO_22") (pintype "bidirectional"))
      (node (ref "U7") (pin "33") (pinfunction "VDDIO_33") (pintype "bidirectional"))
      (node (ref "U7") (pin "42") (pinfunction "VDDIO_42") (pintype "bidirectional"))
      (node (ref "U7") (pin "44") (pinfunction "LDO_IN_44") (pintype "bidirectional"))
      (node (ref "U7") (pin "48") (pinfunction "USB_VDD_48") (pintype "bidirectional"))
      (node (ref "U7") (pin "49") (pinfunction "VDDIO_49") (pintype "bidirectional"))
    )
    (net (code "3") (name "+5V") (class "Default")
      (node (ref "D8") (pin "A") (pinfunction "A_A") (pintype "passive"))
      (node (ref "K1") (pin "2") (pinfunction "2_2") (pintype "passive"))
      (node (ref "K1") (pin "4") (pinfunction "4_4") (pintype "passive"))
      (node (ref "R4") (pin "1") (pinfunction "1_1") (pintype "passive"))
    )
    (net (code "4") (name "1.1V") (class "Default")
      (node (ref "C49") (pin "1") (pinfunction "1_1") (pintype "passive"))
      (node (ref "C50") (pin "1") (pinfunction "1_1") (pintype "passive"))
      (node (ref "C51") (pin "1") (pinfunction "1_1") (pintype "passive"))
      (node (ref "U7") (pin "23") (pinfunction "VDD_1V1_23") (pintype "bidirectional"))
      (node (ref "U7") (pin "45") (pinfunction "LDO_OUT_45") (pintype "bidirectional"))
      (node (ref "U7") (pin "50") (pinfunction "VDD_1V1_50") (pintype "bidirectional"))
    )
    (net (code "5") (name "ALRT") (class "Default")
      (node (ref "R25") (pin "1") (pinfunction "1_1") (pintype "passive"))
      (node (ref "U1") (pin "5") (pinfunction "~{ALERT}_5") (pintype "output"))
    )
    (net (code "6") (name "AVDD") (class "Default")
      (node (ref "C53") (pin "1") (pinfunction "1_1") (pintype "passive"))
      (node (ref "R24") (pin "1") (pinfunction "1_1") (pintype "passive"))
      (node (ref "U7") (pin "43") (pinfunction "ADC_VDD_43") (pintype "bidirectional"))
    )
    (net (code "7") (name "BAT_MON") (class "Default")
      (node (ref "R13") (pin "1") (pinfunction "1_1") (pintype "passive"))
      (node (ref "R14") (pin "2") (pinfunction "2_2") (pintype "passive"))
      (node (ref "U7") (pin "38") (pinfunction "GPIO26/ADC0_38") (pintype "bidirectional"))
    )
    (net (code "8") (name "BOOT") (class "Default")
      (node (ref "R21") (pin "2") (pinfunction "2_2") (pintype "passive"))
      (node (ref "SW4") (pin "B'") (pinfunction "S1_B'") (pintype "passive"))
      (node (ref "U$24") (pin "2") (pinfunction "1_2") (pintype "passive"))
    )
    (net (code "9") (name "CHR_STUS") (class "Default")
      (node (ref "R48") (pin "1") (pinfunction "1_1") (pintype "passive"))
      (node (ref "U5") (pin "1") (pinfunction "STAT_1") (pintype "output"))
    )
    (net (code "10") (name "ECGN") (class "Default")
      (node (ref "C43") (pin "1") (pinfunction "1_1") (pintype "passive"))
      (node (ref "C45") (pin "2") (pinfunction "2_2") (pintype "passive"))
      (node (ref "R40") (pin "2") (pinfunction "2_2") (pintype "passive"))
      (node (ref "U$30") (pin "A6") (pinfunction "INN_A6") (pintype "bidirectional"))
    )
    (net (code "11") (name "ECGN1") (class "Default")
      (node (ref "C66") (pin "1") (pinfunction "1_1") (pintype "passive"))
      (node (ref "JP3") (pin "TIP") (pinfunction "LEFT_TIP") (pintype "bidirectional"))
      (node (ref "R40") (pin "1") (pinfunction "1_1") (pintype "passive"))
      (node (ref "R42") (pin "1") (pinfunction "1_1") (pintype "passive"))
    )
    (net (code "12") (name "ECGP") (class "Default")
      (node (ref "C44") (pin "1") (pinfunction "1_1") (pintype "passive"))
      (node (ref "C45") (pin "1") (pinfunction "1_1") (pintype "passive"))
      (node (ref "R39") (pin "2") (pinfunction "2_2") (pintype "passive"))
      (node (ref "U$30") (pin "A5") (pinfunction "INP_A5") (pintype "bidirectional"))
    )
    (net (code "13") (name "ECGP1") (class "Default")
      (node (ref "C63") (pin "1") (pinfunction "1_1") (pintype "passive"))
      (node (ref "JP3") (pin "RING") (pinfunction "RIGHT_RING") (pintype "bidirectional"))
      (node (ref "R39") (pin "1") (pinfunction "1_1") (pintype "passive"))
      (node (ref "R43") (pin "1") (pinfunction "1_1") (pintype "passive"))
    )
    (net (code "14") (name "ECG_CS") (class "Default")
      (node (ref "U$30") (pin "E6") (pinfunction "CSB_E6") (pintype "bidirectional"))
      (node (ref "U7") (pin "7") (pinfunction "GPIO5_7") (pintype "bidirectional"))
    )
    (net (code "15") (name "ECG_VCM") (class "Default")
      (node (ref "C33") (pin "1") (pinfunction "1_1") (pintype "passive"))
      (node (ref "R41") (pin "1") (pinfunction "1_1") (pintype "passive"))
      (node (ref "U$30") (pin "C1") (pinfunction "VCM_C1") (pintype "bidirectional"))
    )
    (net (code "16") (name "EN") (class "Default")
      (node (ref "K1") (pin "29") (pinfunction "29_29") (pintype "passive"))
      (node (ref "S2") (pin "2") (pinfunction "2-_C_2") (pintype "bidirectional"))
      (node (ref "U$26") (pin "3") (pinfunction "EN_3") (pintype "bidirectional"))
      (node (ref "U3") (pin "3") (pinfunction "EN_3") (pintype "input"))
    )
    (net (code "17") (name "ESP32_CS") (class "Default")
      (node (ref "U4") (pin "16") (pinfunction "IO10_16") (pintype "bidirectional"))
      (node (ref "U7") (pin "12") (pinfunction "GPIO9_12") (pintype "bidirectional"))
    )
    (net (code "18") (name "ESP32_SD_TFT_MISO") (class "Default")
      (node (ref "J4") (pin "7") (pinfunction "DATA0_7") (pintype "bidirectional"))
      (node (ref "K1") (pin "21") (pinfunction "21_21") (pintype "passive"))
      (node (ref "R2") (pin "1") (pinfunction "1_1") (pintype "passive"))
      (node (ref "U7") (pin "11") (pinfunction "GPIO8_11") (pintype "bidirectional"))
    )
    (net (code "19") (name "ESP32_SD_TFT_MOSI") (class "Default")
      (node (ref "J4") (pin "3") (pinfunction "CMD_3") (pintype "bidirectional"))
      (node (ref "K1") (pin "19") (pinfunction "19_19") (pintype "passive"))
      (node (ref "U4") (pin "21") (pinfunction "IO7_21") (pintype "bidirectional"))
      (node (ref "U7") (pin "14") (pinfunction "GPIO11_14") (pintype "bidirectional"))
    )
    (net (code "20") (name "ESP32_SD_TFT_SCK") (class "Default")
      (node (ref "J4") (pin "5") (pinfunction "CLK_5") (pintype "bidirectional"))
      (node (ref "K1") (pin "23") (pinfunction "23_23") (pintype "passive"))
      (node (ref "U4") (pin "20") (pinfunction "IO6_20") (pintype "bidirectional"))
      (node (ref "U7") (pin "13") (pinfunction "GPIO10_13") (pintype "bidirectional"))
    )
    (net (code "21") (name "ESP32_UART_RXD") (class "Default")
      (node (ref "R37") (pin "2") (pinfunction "2_2") (pintype "passive"))
      (node (ref "U4") (pin "30") (pinfunction "RXD0_30") (pintype "bidirectional"))
    )
    (net (code "22") (name "ESP32_UART_TXD") (class "Default")
      (node (ref "R36") (pin "2") (pinfunction "2_2") (pintype "passive"))
      (node (ref "U4") (pin "31") (pinfunction "TXD0_31") (pintype "bidirectional"))
    )
    (net (code "23") (name "ESP_BOOT") (class "Default")
      (node (ref "SW1") (pin "B'") (pinfunction "S1_B'") (pintype "passive"))
      (node (ref "U4") (pin "23") (pinfunction "IO9_23") (pintype "bidirectional"))
    )
    (net (code "24") (name "ESP_RST") (class "Default")
      (node (ref "C4") (pin "2") (pinfunction "2_2") (pintype "passive"))
      (node (ref "R23") (pin "1") (pinfunction "1_1") (pintype "passive"))
      (node (ref "SW2") (pin "B'") (pinfunction "S1_B'") (pintype "passive"))
      (node (ref "U4") (pin "8") (pinfunction "EN_8") (pintype "input"))
    )
    (net (code "25") (name "FCLK") (class "Default")
      (node (ref "TP2") (pin "P$1") (pinfunction "1_P$1") (pintype "bidirectional"))
      (node (ref "U$30") (pin "D5") (pinfunction "FCLK_D5") (pintype "bidirectional"))
      (node (ref "U$31") (pin "3") (pinfunction "CLK_3") (pintype "bidirectional"))
    )
    (net (code "26") (name "GND") (class "Default")
      (node (ref "C1") (pin "2") (pinfunction "2_2") (pintype "passive"))
      (node (ref "C10") (pin "2") (pinfunction "2_2") (pintype "passive"))
      (node (ref "C11") (pin "2") (pinfunction "2_2") (pintype "passive"))
      (node (ref "C12") (pin "2") (pinfunction "2_2") (pintype "passive"))
      (node (ref "C13") (pin "2") (pinfunction "2_2") (pintype "passive"))
      (node (ref "C14") (pin "2") (pinfunction "2_2") (pintype "passive"))
      (node (ref "C15") (pin "1") (pinfunction "1_1") (pintype "passive"))
      (node (ref "C16") (pin "2") (pinfunction "2_2") (pintype "passive"))
      (node (ref "C18") (pin "2") (pinfunction "2_2") (pintype "passive"))
      (node (ref "C19") (pin "2") (pinfunction "2_2") (pintype "passive"))
      (node (ref "C2") (pin "2") (pinfunction "2_2") (pintype "passive"))
      (node (ref "C22") (pin "2") (pinfunction "2_2") (pintype "passive"))
      (node (ref "C24") (pin "2") (pinfunction "2_2") (pintype "passive"))
      (node (ref "C25") (pin "2") (pinfunction "2_2") (pintype "passive"))
      (node (ref "C27") (pin "2") (pinfunction "2_2") (pintype "passive"))
      (node (ref "C28") (pin "2") (pinfunction "2_2") (pintype "passive"))
      (node (ref "C29") (pin "2") (pinfunction "2_2") (pintype "passive"))
      (node (ref "C3") (pin "1") (pinfunction "1_1") (pintype "passive"))
      (node (ref "C30") (pin "2") (pinfunction "2_2") (pintype "passive"))
      (node (ref "C31") (pin "1") (pinfunction "1_1") (pintype "passive"))
      (node (ref "C32") (pin "2") (pinfunction "2_2") (pintype "passive"))
      (node (ref "C33") (pin "2") (pinfunction "2_2") (pintype "passive"))
      (node (ref "C34") (pin "2") (pinfunction "2_2") (pintype "passive"))
      (node (ref "C35") (pin "1") (pinfunction "1_1") (pintype "passive"))
      (node (ref "C36") (pin "1") (pinfunction "1_1") (pintype "passive"))
      (node (ref "C37") (pin "1") (pinfunction "1_1") (pintype "passive"))
      (node (ref "C38") (pin "2") (pinfunction "2_2") (pintype "passive"))
      (node (ref "C39") (pin "2") (pinfunction "2_2") (pintype "passive"))
      (node (ref "C4") (pin "1") (pinfunction "1_1") (pintype "passive"))
      (node (ref "C40") (pin "2") (pinfunction "2_2") (pintype "passive"))
      (node (ref "C41") (pin "2") (pinfunction "2_2") (pintype "passive"))
      (node (ref "C42") (pin "2") (pinfunction "2_2") (pintype "passive"))
      (node (ref "C43") (pin "2") (pinfunction "2_2") (pintype "passive"))
      (node (ref "C44") (pin "2") (pinfunction "2_2") (pintype "passive"))
      (node (ref "C46") (pin "2") (pinfunction "2_2") (pintype "passive"))
      (node (ref "C47") (pin "2") (pinfunction "2_2") (pintype "passive"))
      (node (ref "C48") (pin "2") (pinfunction "2_2") (pintype "passive"))
      (node (ref "C49") (pin "2") (pinfunction "2_2") (pintype "passive"))
      (node (ref "C5") (pin "2") (pinfunction "2_2") (pintype "passive"))
      (node (ref "C50") (pin "2") (pinfunction "2_2") (pintype "passive"))
      (node (ref "C51") (pin "2") (pinfunction "2_2") (pintype "passive"))
      (node (ref "C52") (pin "2") (pinfunction "2_2") (pintype "passive"))
      (node (ref "C53") (pin "2") (pinfunction "2_2") (pintype "passive"))
      (node (ref "C59") (pin "2") (pinfunction "2_2") (pintype "passive"))
      (node (ref "C6") (pin "1") (pinfunction "1_1") (pintype "passive"))
      (node (ref "C64") (pin "2") (pinfunction "2_2") (pintype "passive"))
      (node (ref "C65") (pin "2") (pinfunction "2_2") (pintype "passive"))
      (node (ref "C67") (pin "2") (pinfunction "2_2") (pintype "passive"))
      (node (ref "C68") (pin "2") (pinfunction "2_2") (pintype "passive"))
      (node (ref "C7") (pin "1") (pinfunction "1_1") (pintype "passive"))
      (node (ref "C70") (pin "2") (pinfunction "P$2_2") (pintype "passive"))
      (node (ref "C8") (pin "2") (pinfunction "2_2") (pintype "passive"))
      (node (ref "C9") (pin "2") (pinfunction "2_2") (pintype "passive"))
      (node (ref "D1") (pin "2") (pinfunction "C_2") (pintype "passive"))
      (node (ref "D2") (pin "2") (pinfunction "C_2") (pintype "passive"))
      (node (ref "D3") (pin "2") (pinfunction "C_2") (pintype "passive"))
      (node (ref "D5") (pin "2") (pinfunction "C_2") (pintype "passive"))
      (node (ref "J1") (pin "1") (pinfunction "1_1") (pintype "power_in"))
      (node (ref "J3") (pin "GND") (pinfunction "GND_GND") (pintype "bidirectional"))
      (node (ref "J3") (pin "GND2") (pinfunction "GND_GND2") (pintype "bidirectional"))
      (node (ref "J3") (pin "SHLD1") (pinfunction "SHLD_SHLD1") (pintype "bidirectional"))
      (node (ref "J3") (pin "SHLD2") (pinfunction "SHLD_SHLD2") (pintype "bidirectional"))
      (node (ref "J3") (pin "SHLD3") (pinfunction "SHLD_SHLD3") (pintype "bidirectional"))
      (node (ref "J3") (pin "SHLD4") (pinfunction "SHLD_SHLD4") (pintype "bidirectional"))
      (node (ref "J3") (pin "SHLD5") (pinfunction "SHLD_SHLD5") (pintype "bidirectional"))
      (node (ref "J3") (pin "SHLD6") (pinfunction "SHLD_SHLD6") (pintype "bidirectional"))
      (node (ref "J3") (pin "SHLD7") (pinfunction "SHLD_SHLD7") (pintype "bidirectional"))
      (node (ref "J3") (pin "SHLD8") (pinfunction "SHLD_SHLD8") (pintype "bidirectional"))
      (node (ref "J4") (pin "6") (pinfunction "VSS_6") (pintype "power_in"))
      (node (ref "J5") (pin "GND") (pinfunction "GND_GND") (pintype "bidirectional"))
      (node (ref "J5") (pin "GND2") (pinfunction "GND_GND2") (pintype "bidirectional"))
      (node (ref "J5") (pin "SHLD1") (pinfunction "SHLD_SHLD1") (pintype "bidirectional"))
      (node (ref "J5") (pin "SHLD2") (pinfunction "SHLD_SHLD2") (pintype "bidirectional"))
      (node (ref "J5") (pin "SHLD3") (pinfunction "SHLD_SHLD3") (pintype "bidirectional"))
      (node (ref "J5") (pin "SHLD4") (pinfunction "SHLD_SHLD4") (pintype "bidirectional"))
      (node (ref "J5") (pin "SHLD5") (pinfunction "SHLD_SHLD5") (pintype "bidirectional"))
      (node (ref "J5") (pin "SHLD6") (pinfunction "SHLD_SHLD6") (pintype "bidirectional"))
      (node (ref "J5") (pin "SHLD7") (pinfunction "SHLD_SHLD7") (pintype "bidirectional"))
      (node (ref "J5") (pin "SHLD8") (pinfunction "SHLD_SHLD8") (pintype "bidirectional"))
      (node (ref "J6") (pin "2") (pinfunction "2_2") (pintype "passive"))
      (node (ref "J6") (pin "S1") (pinfunction "SHIELD_S1") (pintype "passive"))
      (node (ref "J6") (pin "S2") (pinfunction "SHIELD_S2") (pintype "passive"))
      (node (ref "J7") (pin "2") (pinfunction "2_2") (pintype "passive"))
      (node (ref "J7") (pin "S1") (pinfunction "SHIELD_S1") (pintype "passive"))
      (node (ref "J7") (pin "S2") (pinfunction "SHIELD_S2") (pintype "passive"))
      (node (ref "JP6") (pin "1") (pinfunction "1_1") (pintype "passive"))
      (node (ref "K1") (pin "14") (pinfunction "14_14") (pintype "passive"))
      (node (ref "K1") (pin "20") (pinfunction "20_20") (pintype "passive"))
      (node (ref "K1") (pin "25") (pinfunction "25_25") (pintype "passive"))
      (node (ref "K1") (pin "30") (pinfunction "30_30") (pintype "passive"))
      (node (ref "K1") (pin "34") (pinfunction "34_34") (pintype "passive"))
      (node (ref "K1") (pin "39") (pinfunction "39_39") (pintype "passive"))
      (node (ref "K1") (pin "6") (pinfunction "6_6") (pintype "passive"))
      (node (ref "K1") (pin "9") (pinfunction "9_9") (pintype "passive"))
      (node (ref "R1") (pin "1") (pinfunction "1_1") (pintype "passive"))
      (node (ref "R11") (pin "1") (pinfunction "1_1") (pintype "passive"))
      (node (ref "R14") (pin "1") (pinfunction "1_1") (pintype "passive"))
      (node (ref "R15") (pin "2") (pinfunction "2_2") (pintype "passive"))
      (node (ref "R16") (pin "2") (pinfunction "2_2") (pintype "passive"))
      (node (ref "R26") (pin "2") (pinfunction "2_2") (pintype "passive"))
      (node (ref "R27") (pin "2") (pinfunction "2_2") (pintype "passive"))
      (node (ref "R30") (pin "1") (pinfunction "1_1") (pintype "passive"))
      (node (ref "R44") (pin "2") (pinfunction "2_2") (pintype "passive"))
      (node (ref "SW1") (pin "A'") (pinfunction "P1_A'") (pintype "passive"))
      (node (ref "SW2") (pin "A'") (pinfunction "P1_A'") (pintype "passive"))
      (node (ref "SW4") (pin "A'") (pinfunction "P1_A'") (pintype "passive"))
      (node (ref "SW5") (pin "A'") (pinfunction "P1_A'") (pintype "passive"))
      (node (ref "U$24") (pin "3") (pinfunction "0_3") (pintype "passive"))
      (node (ref "U$26") (pin "2") (pinfunction "GND_2") (pintype "bidirectional"))
      (node (ref "U$3") (pin "12") (pinfunction "LED_DRV_GND_12") (pintype "bidirectional"))
      (node (ref "U$3") (pin "13") (pinfunction "LED_DRV_GND_13") (pintype "bidirectional"))
      (node (ref "U$3") (pin "16") (pinfunction "LED_DRV_GND_16") (pintype "bidirectional"))
      (node (ref "U$3") (pin "19") (pinfunction "RX_DIG_GND_19") (pintype "bidirectional"))
      (node (ref "U$3") (pin "3") (pinfunction "RX_ANA_GND_3") (pintype "bidirectional"))
      (node (ref "U$3") (pin "32") (pinfunction "RX_DIG_GND_32") (pintype "bidirectional"))
      (node (ref "U$3") (pin "36") (pinfunction "RX_ANA_GND_36") (pintype "bidirectional"))
      (node (ref "U$3") (pin "40") (pinfunction "RX_ANA_GND_40") (pintype "bidirectional"))
      (node (ref "U$3") (pin "8") (pinfunction "VSS_8") (pintype "bidirectional"))
      (node (ref "U$3") (pin "EXP@10") (pinfunction "THER3_EXP@10") (pintype "bidirectional"))
      (node (ref "U$3") (pin "EXP@11") (pinfunction "THER4_EXP@11") (pintype "bidirectional"))
      (node (ref "U$3") (pin "EXP@6") (pinfunction "THER1_EXP@6") (pintype "bidirectional"))
      (node (ref "U$3") (pin "EXP@7") (pinfunction "THER2_EXP@7") (pintype "bidirectional"))
      (node (ref "U$30") (pin "B3") (pinfunction "AGND_B3") (pintype "bidirectional"))
      (node (ref "U$30") (pin "B4") (pinfunction "AGND_B4") (pintype "bidirectional"))
      (node (ref "U$30") (pin "C3") (pinfunction "AGND_C3") (pintype "bidirectional"))
      (node (ref "U$30") (pin "C4") (pinfunction "AGND_C4") (pintype "bidirectional"))
      (node (ref "U$30") (pin "C5") (pinfunction "DGND_C5") (pintype "bidirectional"))
      (node (ref "U$30") (pin "D4") (pinfunction "AGND_D4") (pintype "bidirectional"))
      (node (ref "U$31") (pin "2") (pinfunction "GND_2") (pintype "bidirectional"))
      (node (ref "U$38") (pin "4") (pinfunction "GND_4") (pintype "bidirectional"))
      (node (ref "U$38") (pin "9") (pinfunction "EP_9") (pintype "bidirectional"))
      (node (ref "U1") (pin "1") (pinfunction "CTG_1") (pintype "power_in"))
      (node (ref "U1") (pin "4") (pinfunction "GND_4") (pintype "power_in"))
      (node (ref "U1") (pin "6") (pinfunction "QSTRT_6") (pintype "input"))
      (node (ref "U1") (pin "9") (pinfunction "EP_9") (pintype "power_in"))
      (node (ref "U3") (pin "2") (pinfunction "GND_2") (pintype "input"))
      (node (ref "U4") (pin "1") (pinfunction "GND_1") (pintype "power_in"))
      (node (ref "U4") (pin "11") (pinfunction "GND_11") (pintype "power_in"))
      (node (ref "U4") (pin "14") (pinfunction "GND_14") (pintype "power_in"))
      (node (ref "U4") (pin "2") (pinfunction "GND_2") (pintype "power_in"))
      (node (ref "U4") (pin "36") (pinfunction "GND_36") (pintype "power_in"))
      (node (ref "U4") (pin "37") (pinfunction "GND_37") (pintype "power_in"))
      (node (ref "U4") (pin "38") (pinfunction "GND_38") (pintype "power_in"))
      (node (ref "U4") (pin "39") (pinfunction "GND_39") (pintype "power_in"))
      (node (ref "U4") (pin "40") (pinfunction "GND_40") (pintype "power_in"))
      (node (ref "U4") (pin "41") (pinfunction "GND_41") (pintype "power_in"))
      (node (ref "U4") (pin "42") (pinfunction "GND_42") (pintype "power_in"))
      (node (ref "U4") (pin "43") (pinfunction "GND_43") (pintype "power_in"))
      (node (ref "U4") (pin "44") (pinfunction "GND_44") (pintype "power_in"))
      (node (ref "U4") (pin "45") (pinfunction "GND_45") (pintype "power_in"))
      (node (ref "U4") (pin "46") (pinfunction "GND_46") (pintype "power_in"))
      (node (ref "U4") (pin "47") (pinfunction "GND_47") (pintype "power_in"))
      (node (ref "U4") (pin "48") (pinfunction "GND_48") (pintype "power_in"))
      (node (ref "U4") (pin "49_1") (pinfunction "GND_49_1") (pintype "power_in"))
      (node (ref "U4") (pin "49_2") (pinfunction "GND_49_2") (pintype "power_in"))
      (node (ref "U4") (pin "49_3") (pinfunction "GND_49_3") (pintype "power_in"))
      (node (ref "U4") (pin "49_4") (pinfunction "GND_49_4") (pintype "power_in"))
      (node (ref "U4") (pin "49_5") (pinfunction "GND_49_5") (pintype "power_in"))
      (node (ref "U4") (pin "49_6") (pinfunction "GND_49_6") (pintype "power_in"))
      (node (ref "U4") (pin "49_7") (pinfunction "GND_49_7") (pintype "power_in"))
      (node (ref "U4") (pin "49_8") (pinfunction "GND_49_8") (pintype "power_in"))
      (node (ref "U4") (pin "49_9") (pinfunction "GND_49_9") (pintype "power_in"))
      (node (ref "U4") (pin "50") (pinfunction "GND_50") (pintype "power_in"))
      (node (ref "U4") (pin "51") (pinfunction "GND_51") (pintype "power_in"))
      (node (ref "U4") (pin "52") (pinfunction "GND_52") (pintype "power_in"))
      (node (ref "U4") (pin "53") (pinfunction "GND_53") (pintype "power_in"))
      (node (ref "U5") (pin "2") (pinfunction "VSS_2") (pintype "power_in"))
      (node (ref "U6") (pin "4") (pinfunction "GND_4") (pintype "bidirectional"))
      (node (ref "U7") (pin "19") (pinfunction "TESTEN_19") (pintype "bidirectional"))
      (node (ref "U7") (pin "EPAD") (pinfunction "GND_EPAD") (pintype "bidirectional"))
      (node (ref "X1") (pin "7") (pinfunction "7_7") (pintype "passive"))
      (node (ref "X1") (pin "G1") (pinfunction "P$1_G1") (pintype "bidirectional"))
      (node (ref "X1") (pin "G2") (pinfunction "P$2_G2") (pintype "bidirectional"))
    )
    (net (code "27") (name "INN") (class "Default")
      (node (ref "D3") (pin "1") (pinfunction "CA_1") (pintype "passive"))
      (node (ref "U$3") (pin "1") (pinfunction "INN_1") (pintype "bidirectional"))
      (node (ref "X1") (pin "5") (pinfunction "5_5") (pintype "passive"))
    )
    (net (code "28") (name "INP") (class "Default")
      (node (ref "D2") (pin "1") (pinfunction "CA_1") (pintype "passive"))
      (node (ref "U$3") (pin "2") (pinfunction "INP_2") (pintype "bidirectional"))
      (node (ref "X1") (pin "9") (pinfunction "9_9") (pintype "passive"))
    )
    (net (code "29") (name "INT2B") (class "Default")
      (node (ref "U$30") (pin "E2") (pinfunction "INT2B_E2") (pintype "bidirectional"))
      (node (ref "U7") (pin "30") (pinfunction "GPIO19_30") (pintype "bidirectional"))
    )
    (net (code "30") (name "INTB") (class "Default")
      (node (ref "U$30") (pin "D2") (pinfunction "INTB_D2") (pintype "bidirectional"))
      (node (ref "U7") (pin "31") (pinfunction "GPIO20_31") (pintype "bidirectional"))
    )
    (net (code "31") (name "LED1") (class "Default")
      (node (ref "R51") (pin "2") (pinfunction "2_2") (pintype "passive"))
      (node (ref "U7") (pin "34") (pinfunction "GPIO22_34") (pintype "bidirectional"))
    )
    (net (code "32") (name "LED2") (class "Default")
      (node (ref "R49") (pin "1") (pinfunction "1_1") (pintype "passive"))
      (node (ref "U7") (pin "32") (pinfunction "GPIO21_32") (pintype "bidirectional"))
    )
    (net (code "33") (name "LED_DRV_SUP") (class "Default")
      (node (ref "C10") (pin "1") (pinfunction "1_1") (pintype "passive"))
      (node (ref "C28") (pin "1") (pinfunction "1_1") (pintype "passive"))
      (node (ref "D1") (pin "3") (pinfunction "A_3") (pintype "passive"))
      (node (ref "D5") (pin "3") (pinfunction "A_3") (pintype "passive"))
      (node (ref "U$11") (pin "2") (pinfunction "P$2_2") (pintype "bidirectional"))
      (node (ref "U$3") (pin "17") (pinfunction "LED_DRV_SUP_17") (pintype "bidirectional"))
      (node (ref "U$3") (pin "18") (pinfunction "LED_DRV_SUP_18") (pintype "bidirectional"))
    )
    (net (code "34") (name "MISO") (class "Default")
      (node (ref "U$3") (pin "25") (pinfunction "SPISOMI_25") (pintype "bidirectional"))
      (node (ref "U$30") (pin "E3") (pinfunction "SDO_E3") (pintype "bidirectional"))
      (node (ref "U7") (pin "6") (pinfunction "GPIO4_6") (pintype "bidirectional"))
    )
    (net (code "35") (name "MOSI") (class "Default")
      (node (ref "U$3") (pin "26") (pinfunction "SPISIMO_26") (pintype "bidirectional"))
      (node (ref "U$30") (pin "E4") (pinfunction "SDI_E4") (pintype "bidirectional"))
      (node (ref "U7") (pin "5") (pinfunction "GPIO3_5") (pintype "bidirectional"))
    )
    (net (code "36") (name "Net-(J3-CC1)") (class "Default")
      (node (ref "J3") (pin "A5") (pinfunction "CC1_A5") (pintype "bidirectional"))
      (node (ref "R27") (pin "1") (pinfunction "1_1") (pintype "passive"))
    )
    (net (code "37") (name "Net-(J3-CC2)") (class "Default")
      (node (ref "J3") (pin "B5") (pinfunction "CC2_B5") (pintype "bidirectional"))
      (node (ref "R26") (pin "1") (pinfunction "1_1") (pintype "passive"))
    )
    (net (code "38") (name "Net-(J5-CC1)") (class "Default")
      (node (ref "J5") (pin "A5") (pinfunction "CC1_A5") (pintype "bidirectional"))
      (node (ref "R16") (pin "1") (pinfunction "1_1") (pintype "passive"))
    )
    (net (code "39") (name "Net-(J5-CC2)") (class "Default")
      (node (ref "J5") (pin "B5") (pinfunction "CC2_B5") (pintype "bidirectional"))
      (node (ref "R15") (pin "1") (pinfunction "1_1") (pintype "passive"))
    )
    (net (code "40") (name "Net-(J5-D+-PadA6)") (class "Default")
      (node (ref "J5") (pin "A6") (pinfunction "D+_A6") (pintype "bidirectional"))
      (node (ref "J5") (pin "B6") (pinfunction "D+_B6") (pintype "bidirectional"))
      (node (ref "R8") (pin "1") (pinfunction "1_1") (pintype "passive"))
    )
    (net (code "41") (name "Net-(J5-D--PadA7)") (class "Default")
      (node (ref "J5") (pin "A7") (pinfunction "D-_A7") (pintype "bidirectional"))
      (node (ref "J5") (pin "B7") (pinfunction "D-_B7") (pintype "bidirectional"))
      (node (ref "R10") (pin "1") (pinfunction "1_1") (pintype "passive"))
    )
    (net (code "42") (name "Net-(JP3-PadSLEEVE)") (class "Default")
      (node (ref "JP3") (pin "SLEEVE") (pinfunction "SLEEVE_SLEEVE") (pintype "bidirectional"))
      (node (ref "R41") (pin "2") (pinfunction "2_2") (pintype "passive"))
    )
    (net (code "43") (name "Net-(JP_SW3-Pad3)") (class "Default")
      (node (ref "JP_SW3") (pin "3") (pinfunction "3_3") (pintype "passive"))
      (node (ref "K1") (pin "16") (pinfunction "16_16") (pintype "passive"))
    )
    (net (code "44") (name "Net-(LED1-0)") (class "Default")
      (node (ref "LED1") (pin "1") (pinfunction "0_1") (pintype "passive"))
      (node (ref "LED1") (pin "2") (pinfunction "1_2") (pintype "passive"))
      (node (ref "R49") (pin "2") (pinfunction "2_2") (pintype "passive"))
    )
    (net (code "45") (name "Net-(LED1-3)") (class "Default")
      (node (ref "LED1") (pin "4") (pinfunction "3_4") (pintype "passive"))
      (node (ref "R48") (pin "2") (pinfunction "2_2") (pintype "passive"))
    )
    (net (code "46") (name "Net-(LED1-5)") (class "Default")
      (node (ref "LED1") (pin "6") (pinfunction "5_6") (pintype "passive"))
      (node (ref "R51") (pin "1") (pinfunction "1_1") (pintype "passive"))
    )
    (net (code "47") (name "Net-(Q3-S)") (class "Default")
      (node (ref "C22") (pin "1") (pinfunction "1_1") (pintype "passive"))
      (node (ref "C37") (pin "2") (pinfunction "2_2") (pintype "passive"))
      (node (ref "D10") (pin "C") (pinfunction "C_C") (pintype "passive"))
      (node (ref "Q3") (pin "2") (pinfunction "S_2") (pintype "passive"))
      (node (ref "S2") (pin "3") (pinfunction "3_3") (pintype "bidirectional"))
      (node (ref "U$26") (pin "1") (pinfunction "VIN_1") (pintype "bidirectional"))
      (node (ref "U3") (pin "1") (pinfunction "IN_1") (pintype "input"))
    )
    (net (code "48") (name "Net-(R1-Pad2)") (class "Default")
      (node (ref "R1") (pin "2") (pinfunction "2_2") (pintype "passive"))
      (node (ref "S2") (pin "1") (pinfunction "1_1") (pintype "bidirectional"))
    )
    (net (code "49") (name "Net-(TP4-1)") (class "Default")
      (node (ref "TP4") (pin "P$1") (pinfunction "1_P$1") (pintype "bidirectional"))
      (node (ref "U$3") (pin "30") (pinfunction "CLKOUT_30") (pintype "bidirectional"))
    )
    (net (code "50") (name "Net-(U$3-BG)") (class "Default")
      (node (ref "C8") (pin "1") (pinfunction "1_1") (pintype "passive"))
      (node (ref "U$3") (pin "7") (pinfunction "BG_7") (pintype "bidirectional"))
    )
    (net (code "51") (name "Net-(U$3-XIN)") (class "Default")
      (node (ref "C6") (pin "2") (pinfunction "2_2") (pintype "passive"))
      (node (ref "U$3") (pin "38") (pinfunction "XIN_38") (pintype "bidirectional"))
      (node (ref "U$4") (pin "2") (pinfunction "2_2") (pintype "passive"))
    )
    (net (code "52") (name "Net-(U$3-XOUT)") (class "Default")
      (node (ref "C7") (pin "2") (pinfunction "2_2") (pintype "passive"))
      (node (ref "U$3") (pin "37") (pinfunction "XOUT_37") (pintype "bidirectional"))
      (node (ref "U$4") (pin "1") (pinfunction "1_1") (pintype "passive"))
    )
    (net (code "53") (name "Net-(U$19-1)") (class "Default")
      (node (ref "C1") (pin "1") (pinfunction "1_1") (pintype "passive"))
      (node (ref "U$19") (pin "P$1") (pinfunction "1_P$1") (pintype "passive"))
      (node (ref "U4") (pin "13") (pinfunction "IO1_13") (pintype "bidirectional"))
    )
    (net (code "54") (name "Net-(U$19-2)") (class "Default")
      (node (ref "C15") (pin "2") (pinfunction "2_2") (pintype "passive"))
      (node (ref "U$19") (pin "P$2") (pinfunction "2_P$2") (pintype "passive"))
      (node (ref "U4") (pin "12") (pinfunction "IO0_12") (pintype "bidirectional"))
    )
    (net (code "55") (name "Net-(U$30-BIN)") (class "Default")
      (node (ref "C67") (pin "1") (pinfunction "1_1") (pintype "passive"))
      (node (ref "C69") (pin "1") (pinfunction "1_1") (pintype "passive"))
      (node (ref "R42") (pin "2") (pinfunction "2_2") (pintype "passive"))
      (node (ref "U$30") (pin "A3") (pinfunction "BIN_A3") (pintype "bidirectional"))
    )
    (net (code "56") (name "Net-(U$30-BIP)") (class "Default")
      (node (ref "C68") (pin "1") (pinfunction "1_1") (pintype "passive"))
      (node (ref "C69") (pin "2") (pinfunction "2_2") (pintype "passive"))
      (node (ref "R43") (pin "2") (pinfunction "2_2") (pintype "passive"))
      (node (ref "U$30") (pin "A4") (pinfunction "BIP_A4") (pintype "bidirectional"))
    )
    (net (code "57") (name "Net-(U$30-CAPN)") (class "Default")
      (node (ref "C26") (pin "2") (pinfunction "2_2") (pintype "passive"))
      (node (ref "U$30") (pin "B5") (pinfunction "CAPN_B5") (pintype "bidirectional"))
    )
    (net (code "58") (name "Net-(U$30-CAPP)") (class "Default")
      (node (ref "C26") (pin "1") (pinfunction "1_1") (pintype "passive"))
      (node (ref "U$30") (pin "B6") (pinfunction "CAPP_B6") (pintype "bidirectional"))
    )
    (net (code "59") (name "Net-(U$30-CPLL)") (class "Default")
      (node (ref "C29") (pin "1") (pinfunction "1_1") (pintype "passive"))
      (node (ref "U$30") (pin "C6") (pinfunction "CPLL_C6") (pintype "bidirectional"))
    )
    (net (code "60") (name "Net-(U$30-DRVN)") (class "Default")
      (node (ref "C66") (pin "2") (pinfunction "2_2") (pintype "passive"))
      (node (ref "U$30") (pin "A2") (pinfunction "DRVN_A2") (pintype "bidirectional"))
    )
    (net (code "61") (name "Net-(U$30-DRVP)") (class "Default")
      (node (ref "C63") (pin "2") (pinfunction "2_2") (pintype "passive"))
      (node (ref "U$30") (pin "A1") (pinfunction "DRVP_A1") (pintype "bidirectional"))
    )
    (net (code "62") (name "Net-(U$30-RBIAS)") (class "Default")
      (node (ref "R44") (pin "1") (pinfunction "1_1") (pintype "passive"))
      (node (ref "U$30") (pin "B2") (pinfunction "RBIAS_B2") (pintype "bidirectional"))
    )
    (net (code "63") (name "Net-(U$30-VBG)") (class "Default")
      (node (ref "C34") (pin "1") (pinfunction "1_1") (pintype "passive"))
      (node (ref "U$30") (pin "B1") (pinfunction "VBG_B1") (pintype "bidirectional"))
    )
    (net (code "64") (name "Net-(U$30-VREF)") (class "Default")
      (node (ref "C32") (pin "1") (pinfunction "1_1") (pintype "passive"))
      (node (ref "U$30") (pin "D1") (pinfunction "VREF_D1") (pintype "bidirectional"))
    )
    (net (code "65") (name "Net-(U4-IO2)") (class "Default")
      (node (ref "R2") (pin "2") (pinfunction "2_2") (pintype "passive"))
      (node (ref "U4") (pin "5") (pinfunction "IO2_5") (pintype "bidirectional"))
    )
    (net (code "66") (name "Net-(U4-IO3)") (class "Default")
      (node (ref "SWIO3") (pin "TP") (pinfunction "TP_TP") (pintype "input"))
      (node (ref "U4") (pin "6") (pinfunction "IO3_6") (pintype "bidirectional"))
    )
    (net (code "67") (name "Net-(U4-IO4)") (class "Default")
      (node (ref "SWIO4") (pin "TP") (pinfunction "TP_TP") (pintype "input"))
      (node (ref "U4") (pin "18") (pinfunction "IO4_18") (pintype "bidirectional"))
    )
    (net (code "68") (name "Net-(U4-IO5)") (class "Default")
      (node (ref "SWIO6") (pin "TP") (pinfunction "TP_TP") (pintype "input"))
      (node (ref "U4") (pin "19") (pinfunction "IO5_19") (pintype "bidirectional"))
    )
    (net (code "69") (name "Net-(U4-IO8)") (class "Default")
      (node (ref "SWIO2") (pin "TP") (pinfunction "TP_TP") (pintype "input"))
      (node (ref "U4") (pin "22") (pinfunction "IO8_22") (pintype "bidirectional"))
    )
    (net (code "70") (name "Net-(U5-PROG)") (class "Default")
      (node (ref "R11") (pin "2") (pinfunction "2_2") (pintype "passive"))
      (node (ref "U5") (pin "5") (pinfunction "PROG_5") (pintype "input"))
    )
    (net (code "71") (name "Net-(U7-GPIO0)") (class "Default")
      (node (ref "R3") (pin "1") (pinfunction "1_1") (pintype "passive"))
      (node (ref "U7") (pin "2") (pinfunction "GPIO0_2") (pintype "bidirectional"))
    )
    (net (code "72") (name "Net-(U7-GPIO1)") (class "Default")
      (node (ref "R6") (pin "1") (pinfunction "1_1") (pintype "passive"))
      (node (ref "U7") (pin "3") (pinfunction "GPIO1_3") (pintype "bidirectional"))
    )
    (net (code "73") (name "Net-(U7-GPIO24)") (class "Default")
      (node (ref "R37") (pin "1") (pinfunction "1_1") (pintype "passive"))
      (node (ref "U7") (pin "36") (pinfunction "GPIO24_36") (pintype "bidirectional"))
    )
    (net (code "74") (name "Net-(U7-GPIO25)") (class "Default")
      (node (ref "R36") (pin "1") (pinfunction "1_1") (pintype "passive"))
      (node (ref "U7") (pin "37") (pinfunction "GPIO25_37") (pintype "bidirectional"))
    )
    (net (code "75") (name "Net-(U7-SWCLK)") (class "Default")
      (node (ref "R9") (pin "2") (pinfunction "2_2") (pintype "passive"))
      (node (ref "U7") (pin "24") (pinfunction "SWCLK_24") (pintype "bidirectional"))
    )
    (net (code "76") (name "Net-(U7-SWDIO)") (class "Default")
      (node (ref "R12") (pin "2") (pinfunction "2_2") (pintype "passive"))
      (node (ref "U7") (pin "25") (pinfunction "SWDIO_25") (pintype "bidirectional"))
    )
    (net (code "77") (name "Net-(U7-USB_D+)") (class "Default")
      (node (ref "R20") (pin "2") (pinfunction "2_2") (pintype "passive"))
      (node (ref "U7") (pin "47") (pinfunction "USB_D+_47") (pintype "bidirectional"))
    )
    (net (code "78") (name "Net-(U7-USB_D-)") (class "Default")
      (node (ref "R19") (pin "2") (pinfunction "2_2") (pintype "passive"))
      (node (ref "U7") (pin "46") (pinfunction "USB_D-_46") (pintype "bidirectional"))
    )
    (net (code "79") (name "Net-(U7-XIN)") (class "Default")
      (node (ref "C36") (pin "2") (pinfunction "2_2") (pintype "passive"))
      (node (ref "U7") (pin "20") (pinfunction "XIN_20") (pintype "bidirectional"))
      (node (ref "Y2") (pin "P3") (pinfunction "2_P3") (pintype "passive"))
    )
    (net (code "80") (name "Net-(U7-XOUT)") (class "Default")
      (node (ref "R18") (pin "2") (pinfunction "2_2") (pintype "passive"))
      (node (ref "U7") (pin "21") (pinfunction "XOUT_21") (pintype "bidirectional"))
    )
    (net (code "81") (name "Net-(Y2-1)") (class "Default")
      (node (ref "C31") (pin "2") (pinfunction "2_2") (pintype "passive"))
      (node (ref "R18") (pin "1") (pinfunction "1_1") (pintype "passive"))
      (node (ref "Y2") (pin "P1") (pinfunction "1_P1") (pintype "passive"))
    )
    (net (code "82") (name "QSPI-0") (class "Default")
      (node (ref "U6") (pin "5") (pinfunction "D0/DI_5") (pintype "bidirectional"))
      (node (ref "U7") (pin "53") (pinfunction "QSPI_SD0_53") (pintype "bidirectional"))
    )
    (net (code "83") (name "QSPI-1") (class "Default")
      (node (ref "U6") (pin "2") (pinfunction "D1/DO_2") (pintype "bidirectional"))
      (node (ref "U7") (pin "55") (pinfunction "QSPI_SD1_55") (pintype "bidirectional"))
    )
    (net (code "84") (name "QSPI-2") (class "Default")
      (node (ref "U6") (pin "3") (pinfunction "D2/~{WP}_3") (pintype "bidirectional"))
      (node (ref "U7") (pin "54") (pinfunction "QSPI_SD2_54") (pintype "bidirectional"))
    )
    (net (code "85") (name "QSPI-3") (class "Default")
      (node (ref "U6") (pin "7") (pinfunction "D3/~{HOLD}_7") (pintype "bidirectional"))
      (node (ref "U7") (pin "51") (pinfunction "QSPI_SD3_51") (pintype "bidirectional"))
    )
    (net (code "86") (name "QSPI-CLK") (class "Default")
      (node (ref "U6") (pin "6") (pinfunction "CLK_6") (pintype "bidirectional"))
      (node (ref "U7") (pin "52") (pinfunction "QSPI_SCLK_52") (pintype "bidirectional"))
    )
    (net (code "87") (name "QSPI-CS") (class "Default")
      (node (ref "R21") (pin "1") (pinfunction "1_1") (pintype "passive"))
      (node (ref "R22") (pin "1") (pinfunction "1_1") (pintype "passive"))
      (node (ref "U6") (pin "1") (pinfunction "~{CS}_1") (pintype "bidirectional"))
      (node (ref "U7") (pin "56") (pinfunction "QSPI_~{CS}_56") (pintype "bidirectional"))
    )
    (net (code "88") (name "RP_D+") (class "Default")
      (node (ref "J3") (pin "A6") (pinfunction "D+_A6") (pintype "bidirectional"))
      (node (ref "J3") (pin "B6") (pinfunction "D+_B6") (pintype "bidirectional"))
      (node (ref "R20") (pin "1") (pinfunction "1_1") (pintype "passive"))
    )
    (net (code "89") (name "RP_D-") (class "Default")
      (node (ref "J3") (pin "A7") (pinfunction "D-_A7") (pintype "bidirectional"))
      (node (ref "J3") (pin "B7") (pinfunction "D-_B7") (pintype "bidirectional"))
      (node (ref "R19") (pin "1") (pinfunction "1_1") (pintype "passive"))
    )
    (net (code "90") (name "RX_ANA_SUP") (class "Default")
      (node (ref "C11") (pin "1") (pinfunction "1_1") (pintype "passive"))
      (node (ref "C18") (pin "1") (pinfunction "1_1") (pintype "passive"))
      (node (ref "D2") (pin "3") (pinfunction "A_3") (pintype "passive"))
      (node (ref "D3") (pin "3") (pinfunction "A_3") (pintype "passive"))
      (node (ref "U$3") (pin "33") (pinfunction "RX_ANA_SUP_33") (pintype "bidirectional"))
      (node (ref "U$3") (pin "39") (pinfunction "RX_ANA_SUP_39") (pintype "bidirectional"))
      (node (ref "U$7") (pin "2") (pinfunction "P$2_2") (pintype "bidirectional"))
    )
    (net (code "91") (name "RX_DIG_SUP") (class "Default")
      (node (ref "C12") (pin "1") (pinfunction "1_1") (pintype "passive"))
      (node (ref "C19") (pin "1") (pinfunction "1_1") (pintype "passive"))
      (node (ref "R47") (pin "1") (pinfunction "1_1") (pintype "passive"))
      (node (ref "U$3") (pin "31") (pinfunction "RX_DIG_SUP_31") (pintype "bidirectional"))
      (node (ref "U$9") (pin "2") (pinfunction "P$2_2") (pintype "bidirectional"))
    )
    (net (code "92") (name "SCK") (class "Default")
      (node (ref "U$3") (pin "24") (pinfunction "SCLK_24") (pintype "bidirectional"))
      (node (ref "U$30") (pin "E5") (pinfunction "SCLK_E5") (pintype "bidirectional"))
      (node (ref "U7") (pin "4") (pinfunction "GPIO2_4") (pintype "bidirectional"))
    )
    (net (code "93") (name "SD_CS") (class "Default")
      (node (ref "J4") (pin "2") (pinfunction "DATA3/CD_2") (pintype "bidirectional"))
      (node (ref "R5") (pin "1") (pinfunction "1_1") (pintype "passive"))
      (node (ref "U7") (pin "16") (pinfunction "GPIO13_16") (pintype "bidirectional"))
    )
    (net (code "94") (name "SPO2_CS") (class "Default")
      (node (ref "U$3") (pin "27") (pinfunction "SPISTE_27") (pintype "bidirectional"))
      (node (ref "U7") (pin "39") (pinfunction "GPIO27/ADC1_39") (pintype "bidirectional"))
    )
    (net (code "95") (name "SPO2_DRDY") (class "Default")
      (node (ref "U$3") (pin "28") (pinfunction "ADC_RDY_28") (pintype "bidirectional"))
      (node (ref "U7") (pin "28") (pinfunction "GPIO17_28") (pintype "bidirectional"))
    )
    (net (code "96") (name "SPO2_START") (class "Default")
      (node (ref "U$3") (pin "20") (pinfunction "AFE_~{PDN}_20") (pintype "bidirectional"))
      (node (ref "U7") (pin "29") (pinfunction "GPIO18_29") (pintype "bidirectional"))
    )
    (net (code "97") (name "SW1") (class "Default")
      (node (ref "K1") (pin "26") (pinfunction "26_26") (pintype "passive"))
      (node (ref "U7") (pin "15") (pinfunction "GPIO12_15") (pintype "bidirectional"))
    )
    (net (code "98") (name "SW2") (class "Default")
      (node (ref "K1") (pin "31") (pinfunction "31_31") (pintype "passive"))
      (node (ref "U7") (pin "17") (pinfunction "GPIO14_17") (pintype "bidirectional"))
    )
    (net (code "99") (name "SW3") (class "Default")
      (node (ref "JP_SW3") (pin "2") (pinfunction "2_2") (pintype "passive"))
      (node (ref "U7") (pin "18") (pinfunction "GPIO15_18") (pintype "bidirectional"))
    )
    (net (code "100") (name "SWDCK") (class "Default")
      (node (ref "J6") (pin "1") (pinfunction "1_1") (pintype "passive"))
      (node (ref "R9") (pin "1") (pinfunction "1_1") (pintype "passive"))
    )
    (net (code "101") (name "SWDIO") (class "Default")
      (node (ref "J6") (pin "3") (pinfunction "3_3") (pintype "passive"))
      (node (ref "R12") (pin "1") (pinfunction "1_1") (pintype "passive"))
    )
    (net (code "102") (name "TFT_BKL") (class "Default")
      (node (ref "K1") (pin "12") (pinfunction "12_12") (pintype "passive"))
      (node (ref "U7") (pin "27") (pinfunction "GPIO16_27") (pintype "bidirectional"))
    )
    (net (code "103") (name "TFT_CS") (class "Default")
      (node (ref "K1") (pin "24") (pinfunction "24_24") (pintype "passive"))
      (node (ref "U7") (pin "41") (pinfunction "GPIO29/ADC3_41") (pintype "bidirectional"))
    )
    (net (code "104") (name "TFT_DC") (class "Default")
      (node (ref "K1") (pin "22") (pinfunction "22_22") (pintype "passive"))
      (node (ref "U7") (pin "35") (pinfunction "GPIO23_35") (pintype "bidirectional"))
    )
    (net (code "105") (name "TFT_RESET") (class "Default")
      (node (ref "K1") (pin "36") (pinfunction "36_36") (pintype "passive"))
      (node (ref "U7") (pin "40") (pinfunction "GPIO28/ADC2_40") (pintype "bidirectional"))
    )
    (net (code "106") (name "TMP_SCL") (class "Default")
      (node (ref "J1") (pin "4") (pinfunction "4_4") (pintype "passive"))
      (node (ref "K1") (pin "5") (pinfunction "5_5") (pintype "passive"))
      (node (ref "R7") (pin "2") (pinfunction "2_2") (pintype "passive"))
      (node (ref "U$38") (pin "6") (pinfunction "SCL_6") (pintype "bidirectional"))
      (node (ref "U1") (pin "7") (pinfunction "SCL_7") (pintype "input"))
      (node (ref "U7") (pin "9") (pinfunction "GPIO7_9") (pintype "bidirectional"))
    )
    (net (code "107") (name "TMP_SDA") (class "Default")
      (node (ref "J1") (pin "3") (pinfunction "3_3") (pintype "passive"))
      (node (ref "K1") (pin "3") (pinfunction "3_3") (pintype "passive"))
      (node (ref "R33") (pin "2") (pinfunction "2_2") (pintype "passive"))
      (node (ref "U$38") (pin "5") (pinfunction "SDA_5") (pintype "bidirectional"))
      (node (ref "U1") (pin "8") (pinfunction "SDA_8") (pintype "bidirectional"))
      (node (ref "U7") (pin "8") (pinfunction "GPIO6_8") (pintype "bidirectional"))
    )
    (net (code "108") (name "TXN") (class "Default")
      (node (ref "D1") (pin "1") (pinfunction "CA_1") (pintype "passive"))
      (node (ref "U$3") (pin "14") (pinfunction "TXN_14") (pintype "bidirectional"))
      (node (ref "X1") (pin "3") (pinfunction "3_3") (pintype "passive"))
    )
    (net (code "109") (name "TXP") (class "Default")
      (node (ref "D5") (pin "1") (pinfunction "CA_1") (pintype "passive"))
      (node (ref "U$3") (pin "15") (pinfunction "TXP_15") (pintype "bidirectional"))
      (node (ref "X1") (pin "2") (pinfunction "2_2") (pintype "passive"))
    )
    (net (code "110") (name "TX_CTRL_SUP") (class "Default")
      (node (ref "C27") (pin "1") (pinfunction "1_1") (pintype "passive"))
      (node (ref "C9") (pin "1") (pinfunction "1_1") (pintype "passive"))
      (node (ref "U$10") (pin "2") (pinfunction "P$2_2") (pintype "bidirectional"))
      (node (ref "U$3") (pin "11") (pinfunction "TX_CTRL_SUP_11") (pintype "bidirectional"))
    )
    (net (code "111") (name "U0RXD") (class "Default")
      (node (ref "J7") (pin "1") (pinfunction "1_1") (pintype "passive"))
      (node (ref "JP_SW3") (pin "1") (pinfunction "1_1") (pintype "passive"))
      (node (ref "K1") (pin "8") (pinfunction "8_8") (pintype "passive"))
      (node (ref "R6") (pin "2") (pinfunction "2_2") (pintype "passive"))
    )
    (net (code "112") (name "U0TXD") (class "Default")
      (node (ref "J7") (pin "3") (pinfunction "3_3") (pintype "passive"))
      (node (ref "K1") (pin "10") (pinfunction "10_10") (pintype "passive"))
      (node (ref "R3") (pin "2") (pinfunction "2_2") (pintype "passive"))
    )
    (net (code "113") (name "USB_D+") (class "Default")
      (node (ref "R8") (pin "2") (pinfunction "2_2") (pintype "passive"))
      (node (ref "U4") (pin "27") (pinfunction "IO19_27") (pintype "bidirectional"))
    )
    (net (code "114") (name "USB_D-") (class "Default")
      (node (ref "R10") (pin "2") (pinfunction "2_2") (pintype "passive"))
      (node (ref "U4") (pin "26") (pinfunction "IO18_26") (pintype "bidirectional"))
    )
    (net (code "115") (name "VBAT") (class "Default")
      (node (ref "C5") (pin "1") (pinfunction "1_1") (pintype "passive"))
      (node (ref "C65") (pin "1") (pinfunction "1_1") (pintype "passive"))
      (node (ref "JP6") (pin "2") (pinfunction "2_2") (pintype "passive"))
      (node (ref "Q3") (pin "3") (pinfunction "D_3") (pintype "passive"))
      (node (ref "R13") (pin "2") (pinfunction "2_2") (pintype "passive"))
      (node (ref "U1") (pin "2") (pinfunction "CELL_2") (pintype "power_in"))
      (node (ref "U1") (pin "3") (pinfunction "VDD_3") (pintype "power_in"))
      (node (ref "U5") (pin "3") (pinfunction "VBAT_3") (pintype "power_in"))
    )
    (net (code "116") (name "VBUS") (class "Default")
      (node (ref "D9") (pin "A") (pinfunction "A_A") (pintype "passive"))
      (node (ref "J3") (pin "VBUS1") (pinfunction "VBUS_VBUS1") (pintype "bidirectional"))
      (node (ref "J3") (pin "VBUS2") (pinfunction "VBUS_VBUS2") (pintype "bidirectional"))
      (node (ref "J5") (pin "VBUS1") (pinfunction "VBUS_VBUS1") (pintype "bidirectional"))
      (node (ref "J5") (pin "VBUS2") (pinfunction "VBUS_VBUS2") (pintype "bidirectional"))
      (node (ref "TP5") (pin "TP") (pinfunction "TP_TP") (pintype "input"))
    )
    (net (code "117") (name "VCM") (class "Default")
      (node (ref "C13") (pin "1") (pinfunction "1_1") (pintype "passive"))
      (node (ref "U$3") (pin "4") (pinfunction "VCM_4") (pintype "bidirectional"))
    )
    (net (code "118") (name "VDD") (class "Default")
      (node (ref "C64") (pin "1") (pinfunction "1_1") (pintype "passive"))
      (node (ref "D10") (pin "A") (pinfunction "A_A") (pintype "passive"))
      (node (ref "D8") (pin "C") (pinfunction "C_C") (pintype "passive"))
      (node (ref "D9") (pin "C") (pinfunction "C_C") (pintype "passive"))
      (node (ref "LED1") (pin "5") (pinfunction "4_5") (pintype "passive"))
      (node (ref "Q3") (pin "1") (pinfunction "G_1") (pintype "passive"))
      (node (ref "R30") (pin "2") (pinfunction "2_2") (pintype "passive"))
      (node (ref "R4") (pin "2") (pinfunction "2_2") (pintype "passive"))
      (node (ref "SWIO7") (pin "TP") (pinfunction "TP_TP") (pintype "input"))
      (node (ref "U5") (pin "4") (pinfunction "VIN_4") (pintype "power_in"))
    )
    (net (code "119") (name "unconnected-(J4-DATA1-Pad8)") (class "Default")
      (node (ref "J4") (pin "8") (pinfunction "DATA1_8") (pintype "bidirectional"))
    )
    (net (code "120") (name "unconnected-(J4-DATA2-Pad1)") (class "Default")
      (node (ref "J4") (pin "1") (pinfunction "DATA2_1") (pintype "bidirectional"))
    )
    (net (code "121") (name "unconnected-(J4-DETECH-Pad9)") (class "Default")
      (node (ref "J4") (pin "9") (pinfunction "DETECH_9") (pintype "passive"))
    )
    (net (code "122") (name "unconnected-(K1-Pad7)") (class "Default")
      (node (ref "K1") (pin "7") (pinfunction "7_7") (pintype "passive"))
    )
    (net (code "123") (name "unconnected-(K1-Pad11)") (class "Default")
      (node (ref "K1") (pin "11") (pinfunction "11_11") (pintype "passive"))
    )
    (net (code "124") (name "unconnected-(K1-Pad13)") (class "Default")
      (node (ref "K1") (pin "13") (pinfunction "13_13") (pintype "passive"))
    )
    (net (code "125") (name "unconnected-(K1-Pad15)") (class "Default")
      (node (ref "K1") (pin "15") (pinfunction "15_15") (pintype "passive"))
    )
    (net (code "126") (name "unconnected-(K1-Pad18)") (class "Default")
      (node (ref "K1") (pin "18") (pinfunction "18_18") (pintype "passive"))
    )
    (net (code "127") (name "unconnected-(K1-Pad27)") (class "Default")
      (node (ref "K1") (pin "27") (pinfunction "27_27") (pintype "passive"))
    )
    (net (code "128") (name "unconnected-(K1-Pad28)") (class "Default")
      (node (ref "K1") (pin "28") (pinfunction "28_28") (pintype "passive"))
    )
    (net (code "129") (name "unconnected-(K1-Pad32)") (class "Default")
      (node (ref "K1") (pin "32") (pinfunction "32_32") (pintype "passive"))
    )
    (net (code "130") (name "unconnected-(K1-Pad33)") (class "Default")
      (node (ref "K1") (pin "33") (pinfunction "33_33") (pintype "passive"))
    )
    (net (code "131") (name "unconnected-(K1-Pad35)") (class "Default")
      (node (ref "K1") (pin "35") (pinfunction "35_35") (pintype "passive"))
    )
    (net (code "132") (name "unconnected-(K1-Pad37)") (class "Default")
      (node (ref "K1") (pin "37") (pinfunction "37_37") (pintype "passive"))
    )
    (net (code "133") (name "unconnected-(K1-Pad38)") (class "Default")
      (node (ref "K1") (pin "38") (pinfunction "38_38") (pintype "passive"))
    )
    (net (code "134") (name "unconnected-(K1-Pad40)") (class "Default")
      (node (ref "K1") (pin "40") (pinfunction "40_40") (pintype "passive"))
    )
    (net (code "135") (name "unconnected-(S2-5-Pad4)") (class "Default")
      (node (ref "S2") (pin "4") (pinfunction "5_4") (pintype "bidirectional"))
    )
    (net (code "136") (name "unconnected-(S2-6_-_C-Pad5)") (class "Default")
      (node (ref "S2") (pin "5") (pinfunction "6_-_C_5") (pintype "bidirectional"))
    )
    (net (code "137") (name "unconnected-(S2-7-Pad6)") (class "Default")
      (node (ref "S2") (pin "6") (pinfunction "7_6") (pintype "bidirectional"))
    )
    (net (code "138") (name "unconnected-(SW1-P-PadA)") (class "Default")
      (node (ref "SW1") (pin "A") (pinfunction "P_A") (pintype "passive"))
    )
    (net (code "139") (name "unconnected-(SW1-S-PadB)") (class "Default")
      (node (ref "SW1") (pin "B") (pinfunction "S_B") (pintype "passive"))
    )
    (net (code "140") (name "unconnected-(SW2-P-PadA)") (class "Default")
      (node (ref "SW2") (pin "A") (pinfunction "P_A") (pintype "passive"))
    )
    (net (code "141") (name "unconnected-(SW2-S-PadB)") (class "Default")
      (node (ref "SW2") (pin "B") (pinfunction "S_B") (pintype "passive"))
    )
    (net (code "142") (name "unconnected-(SW4-P-PadA)") (class "Default")
      (node (ref "SW4") (pin "A") (pinfunction "P_A") (pintype "passive"))
    )
    (net (code "143") (name "unconnected-(SW4-S-PadB)") (class "Default")
      (node (ref "SW4") (pin "B") (pinfunction "S_B") (pintype "passive"))
    )
    (net (code "144") (name "unconnected-(SW5-P-PadA)") (class "Default")
      (node (ref "SW5") (pin "A") (pinfunction "P_A") (pintype "passive"))
    )
    (net (code "145") (name "unconnected-(SW5-S-PadB)") (class "Default")
      (node (ref "SW5") (pin "B") (pinfunction "S_B") (pintype "passive"))
    )
    (net (code "146") (name "unconnected-(U$3-DIAG_END-Pad21)") (class "Default")
      (node (ref "U$3") (pin "21") (pinfunction "DIAG_END_21") (pintype "bidirectional"))
    )
    (net (code "147") (name "unconnected-(U$3-DNC-Pad5)") (class "Default")
      (node (ref "U$3") (pin "5") (pinfunction "DNC_5") (pintype "bidirectional"))
    )
    (net (code "148") (name "unconnected-(U$3-DNC-Pad6)") (class "Default")
      (node (ref "U$3") (pin "6") (pinfunction "DNC_6") (pintype "bidirectional"))
    )
    (net (code "149") (name "unconnected-(U$3-DNC-Pad10)") (class "Default")
      (node (ref "U$3") (pin "10") (pinfunction "DNC_10") (pintype "bidirectional"))
    )
    (net (code "150") (name "unconnected-(U$3-DNC-Pad34)") (class "Default")
      (node (ref "U$3") (pin "34") (pinfunction "DNC_34") (pintype "bidirectional"))
    )
    (net (code "151") (name "unconnected-(U$3-DNC-Pad35)") (class "Default")
      (node (ref "U$3") (pin "35") (pinfunction "DNC_35") (pintype "bidirectional"))
    )
    (net (code "152") (name "unconnected-(U$3-LED_ALM-Pad22)") (class "Default")
      (node (ref "U$3") (pin "22") (pinfunction "LED_ALM_22") (pintype "bidirectional"))
    )
    (net (code "153") (name "unconnected-(U$3-PD_ALM-Pad23)") (class "Default")
      (node (ref "U$3") (pin "23") (pinfunction "PD_ALM_23") (pintype "bidirectional"))
    )
    (net (code "154") (name "unconnected-(U$3-RSVD-Pad9)") (class "Default")
      (node (ref "U$3") (pin "9") (pinfunction "RSVD_9") (pintype "bidirectional"))
    )
    (net (code "155") (name "unconnected-(U$24-0-Pad1)") (class "Default")
      (node (ref "U$24") (pin "1") (pinfunction "0_1") (pintype "passive"))
    )
    (net (code "156") (name "unconnected-(U$24-1-Pad4)") (class "Default")
      (node (ref "U$24") (pin "4") (pinfunction "1_4") (pintype "passive"))
    )
    (net (code "157") (name "unconnected-(U$26-NC-Pad4)") (class "Default")
      (node (ref "U$26") (pin "4") (pinfunction "NC_4") (pintype "bidirectional"))
    )
    (net (code "158") (name "unconnected-(U$30-AOUT-PadC2)") (class "Default")
      (node (ref "U$30") (pin "C2") (pinfunction "AOUT_C2") (pintype "bidirectional"))
    )
    (net (code "159") (name "unconnected-(U$31-NC-Pad1)") (class "Default")
      (node (ref "U$31") (pin "1") (pinfunction "NC_1") (pintype "bidirectional"))
    )
    (net (code "160") (name "unconnected-(U$38-NC-Pad1)") (class "Default")
      (node (ref "U$38") (pin "1") (pinfunction "NC_1") (pintype "bidirectional"))
    )
    (net (code "161") (name "unconnected-(U$38-NC-Pad2)") (class "Default")
      (node (ref "U$38") (pin "2") (pinfunction "NC_2") (pintype "bidirectional"))
    )
    (net (code "162") (name "unconnected-(U$38-NC-Pad3)") (class "Default")
      (node (ref "U$38") (pin "3") (pinfunction "NC_3") (pintype "bidirectional"))
    )
    (net (code "163") (name "unconnected-(U$38-NC-Pad7)") (class "Default")
      (node (ref "U$38") (pin "7") (pinfunction "NC_7") (pintype "bidirectional"))
    )
    (net (code "164") (name "unconnected-(U3-BP-Pad4)") (class "Default")
      (node (ref "U3") (pin "4") (pinfunction "BP_4") (pintype "input"))
    )
    (net (code "165") (name "unconnected-(U4-NC-Pad4)") (class "Default")
      (node (ref "U4") (pin "4") (pinfunction "NC_4") (pintype "no_connect"))
    )
    (net (code "166") (name "unconnected-(U4-NC-Pad7)") (class "Default")
      (node (ref "U4") (pin "7") (pinfunction "NC_7") (pintype "no_connect"))
    )
    (net (code "167") (name "unconnected-(U4-NC-Pad9)") (class "Default")
      (node (ref "U4") (pin "9") (pinfunction "NC_9") (pintype "no_connect"))
    )
    (net (code "168") (name "unconnected-(U4-NC-Pad10)") (class "Default")
      (node (ref "U4") (pin "10") (pinfunction "NC_10") (pintype "no_connect"))
    )
    (net (code "169") (name "unconnected-(U4-NC-Pad15)") (class "Default")
      (node (ref "U4") (pin "15") (pinfunction "NC_15") (pintype "no_connect"))
    )
    (net (code "170") (name "unconnected-(U4-NC-Pad17)") (class "Default")
      (node (ref "U4") (pin "17") (pinfunction "NC_17") (pintype "no_connect"))
    )
    (net (code "171") (name "unconnected-(U4-NC-Pad24)") (class "Default")
      (node (ref "U4") (pin "24") (pinfunction "NC_24") (pintype "no_connect"))
    )
    (net (code "172") (name "unconnected-(U4-NC-Pad25)") (class "Default")
      (node (ref "U4") (pin "25") (pinfunction "NC_25") (pintype "no_connect"))
    )
    (net (code "173") (name "unconnected-(U4-NC-Pad28)") (class "Default")
      (node (ref "U4") (pin "28") (pinfunction "NC_28") (pintype "no_connect"))
    )
    (net (code "174") (name "unconnected-(U4-NC-Pad29)") (class "Default")
      (node (ref "U4") (pin "29") (pinfunction "NC_29") (pintype "no_connect"))
    )
    (net (code "175") (name "unconnected-(U4-NC-Pad32)") (class "Default")
      (node (ref "U4") (pin "32") (pinfunction "NC_32") (pintype "no_connect"))
    )
    (net (code "176") (name "unconnected-(U4-NC-Pad33)") (class "Default")
      (node (ref "U4") (pin "33") (pinfunction "NC_33") (pintype "no_connect"))
    )
    (net (code "177") (name "unconnected-(U4-NC-Pad34)") (class "Default")
      (node (ref "U4") (pin "34") (pinfunction "NC_34") (pintype "no_connect"))
    )
    (net (code "178") (name "unconnected-(U4-NC-Pad35)") (class "Default")
      (node (ref "U4") (pin "35") (pinfunction "NC_35") (pintype "no_connect"))
    )
    (net (code "179") (name "unconnected-(X1-Pad1)") (class "Default")
      (node (ref "X1") (pin "1") (pinfunction "1_1") (pintype "passive"))
    )
    (net (code "180") (name "unconnected-(X1-Pad4)") (class "Default")
      (node (ref "X1") (pin "4") (pinfunction "4_4") (pintype "passive"))
    )
    (net (code "181") (name "unconnected-(X1-Pad6)") (class "Default")
      (node (ref "X1") (pin "6") (pinfunction "6_6") (pintype "passive"))
    )
    (net (code "182") (name "unconnected-(X1-Pad8)") (class "Default")
      (node (ref "X1") (pin "8") (pinfunction "8_8") (pintype "passive"))
    )
    (net (code "183") (name "~{ADC_RESET}") (class "Default")
      (node (ref "R47") (pin "2") (pinfunction "2_2") (pintype "passive"))
      (node (ref "U$3") (pin "29") (pinfunction "~{RESET}_29") (pintype "bidirectional"))
    )
    (net (code "184") (name "~{RESET}") (class "Default")
      (node (ref "SW5") (pin "B'") (pinfunction "S1_B'") (pintype "passive"))
      (node (ref "U7") (pin "26") (pinfunction "RUN_26") (pintype "bidirectional"))
    )
  )
)
